# task_eagle.net
KiCad netlist of a schematic drawn in EAGLE
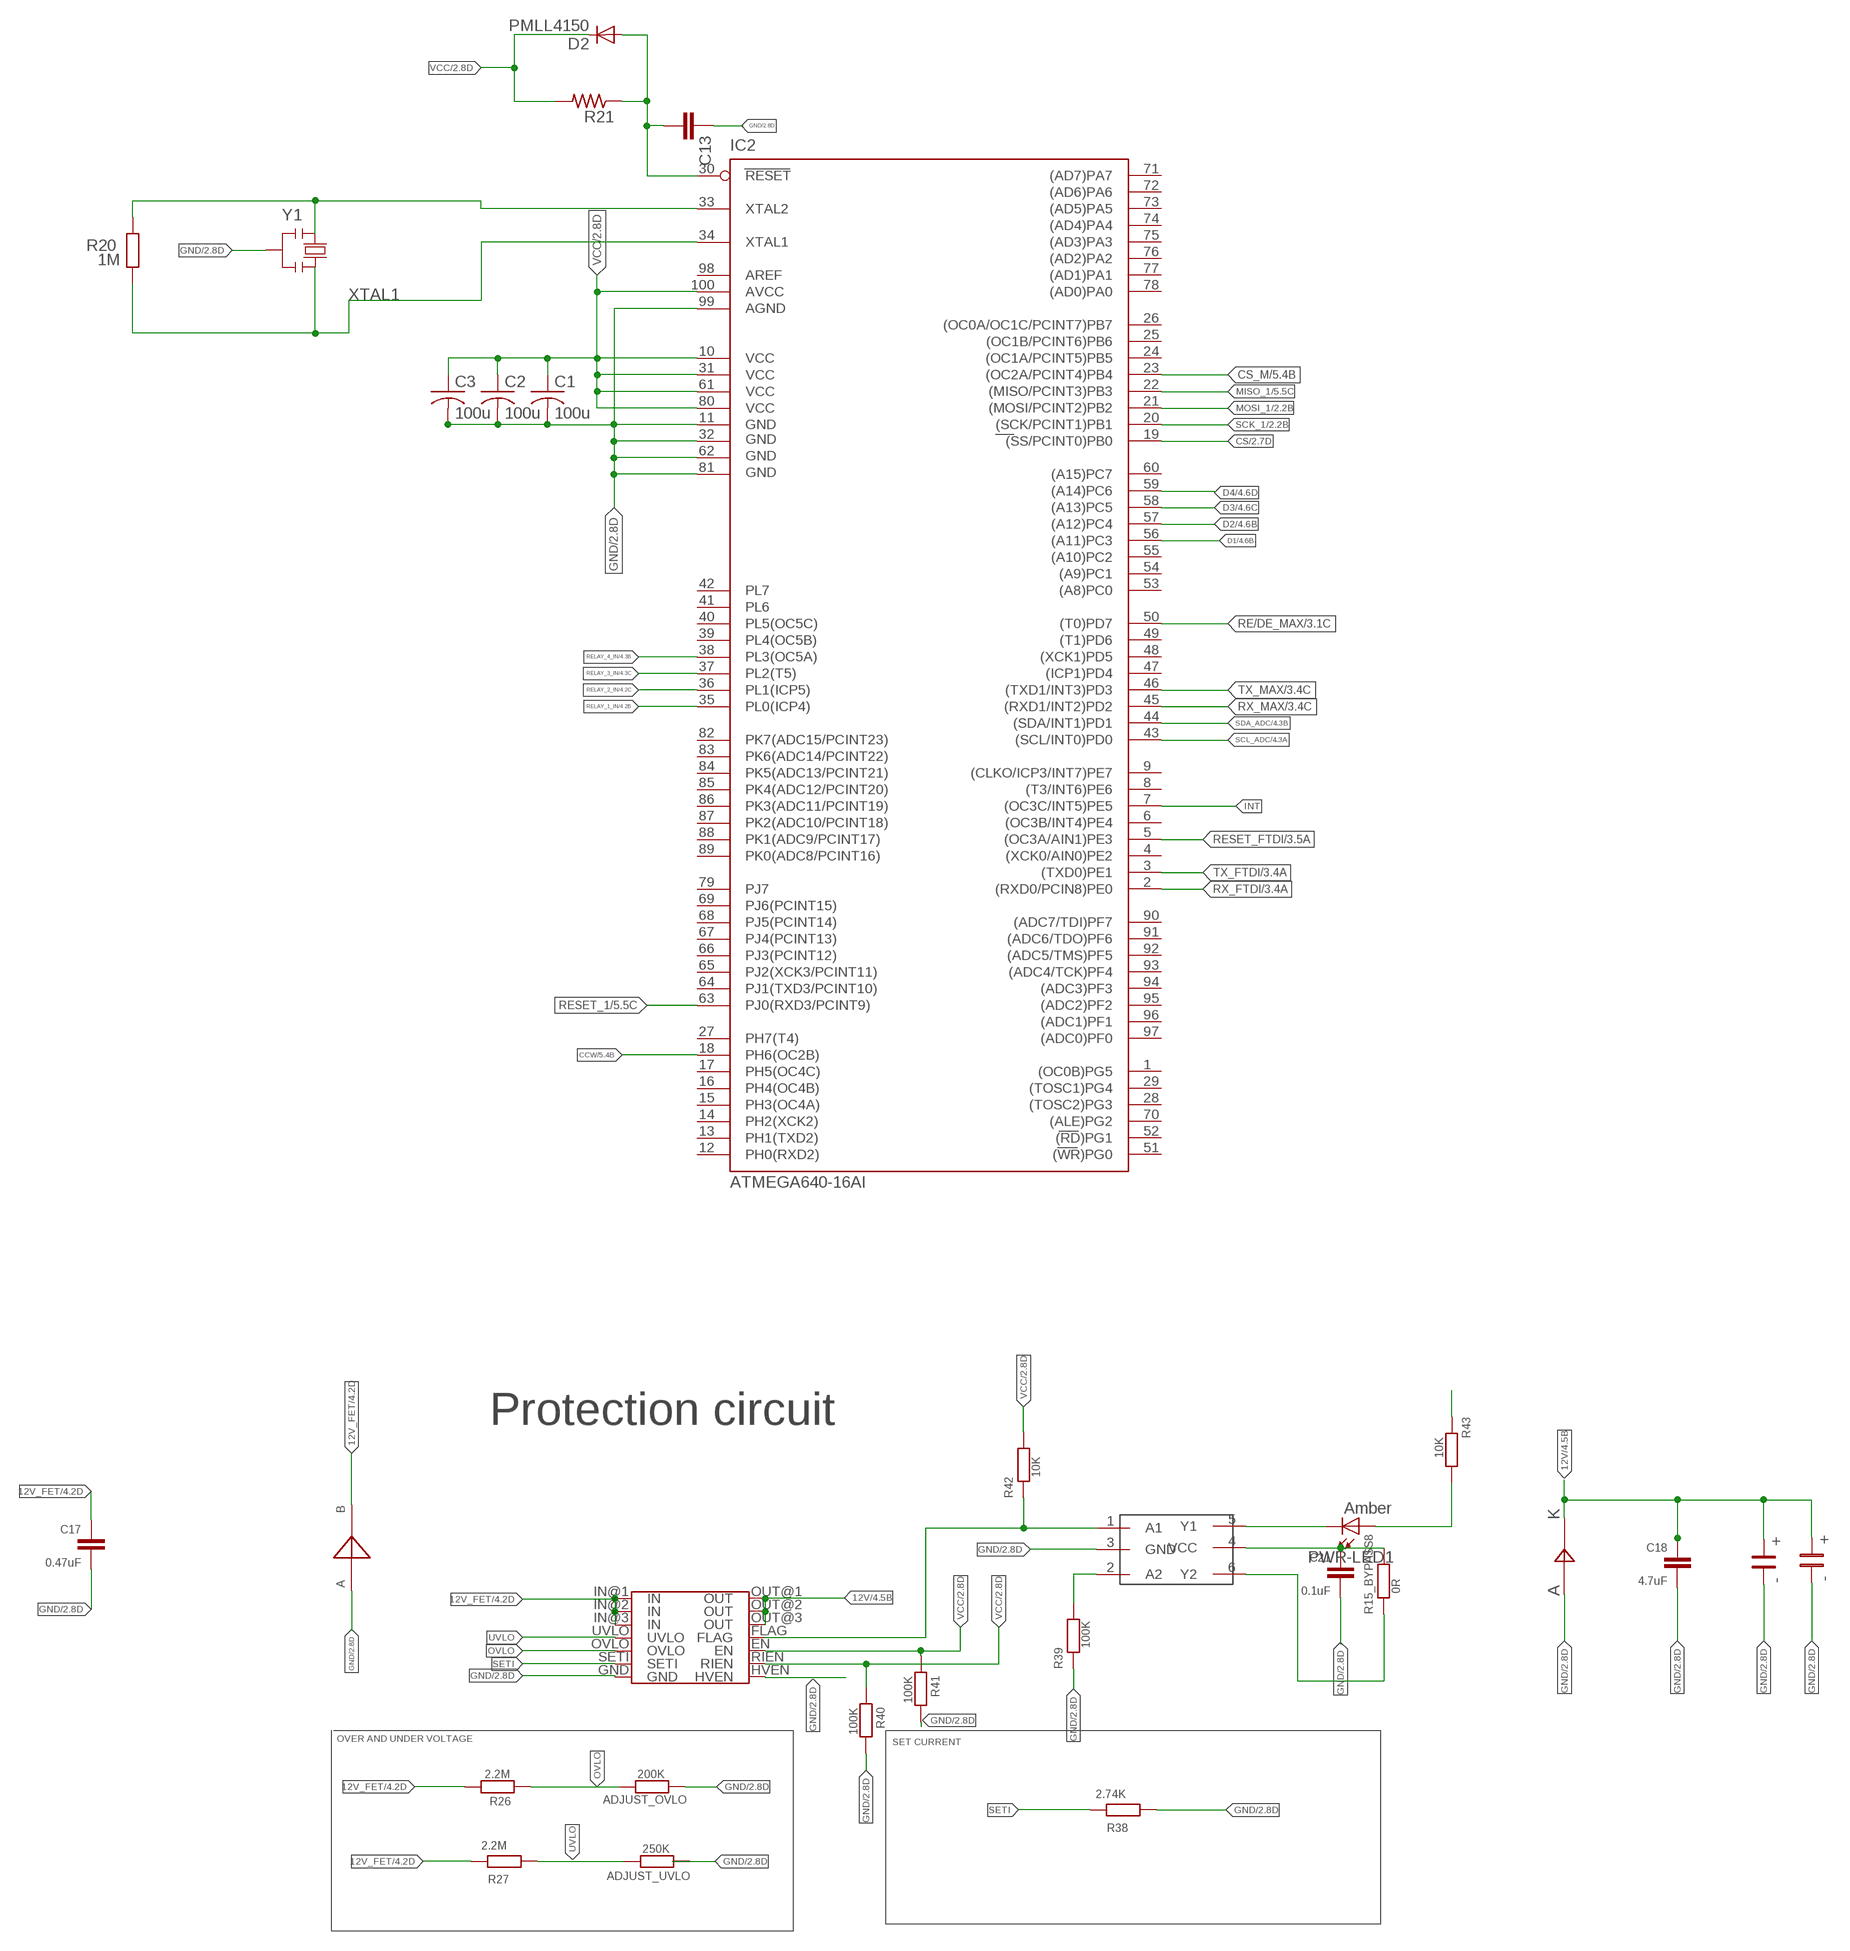
[diagram p0: schematic, sheet 1]
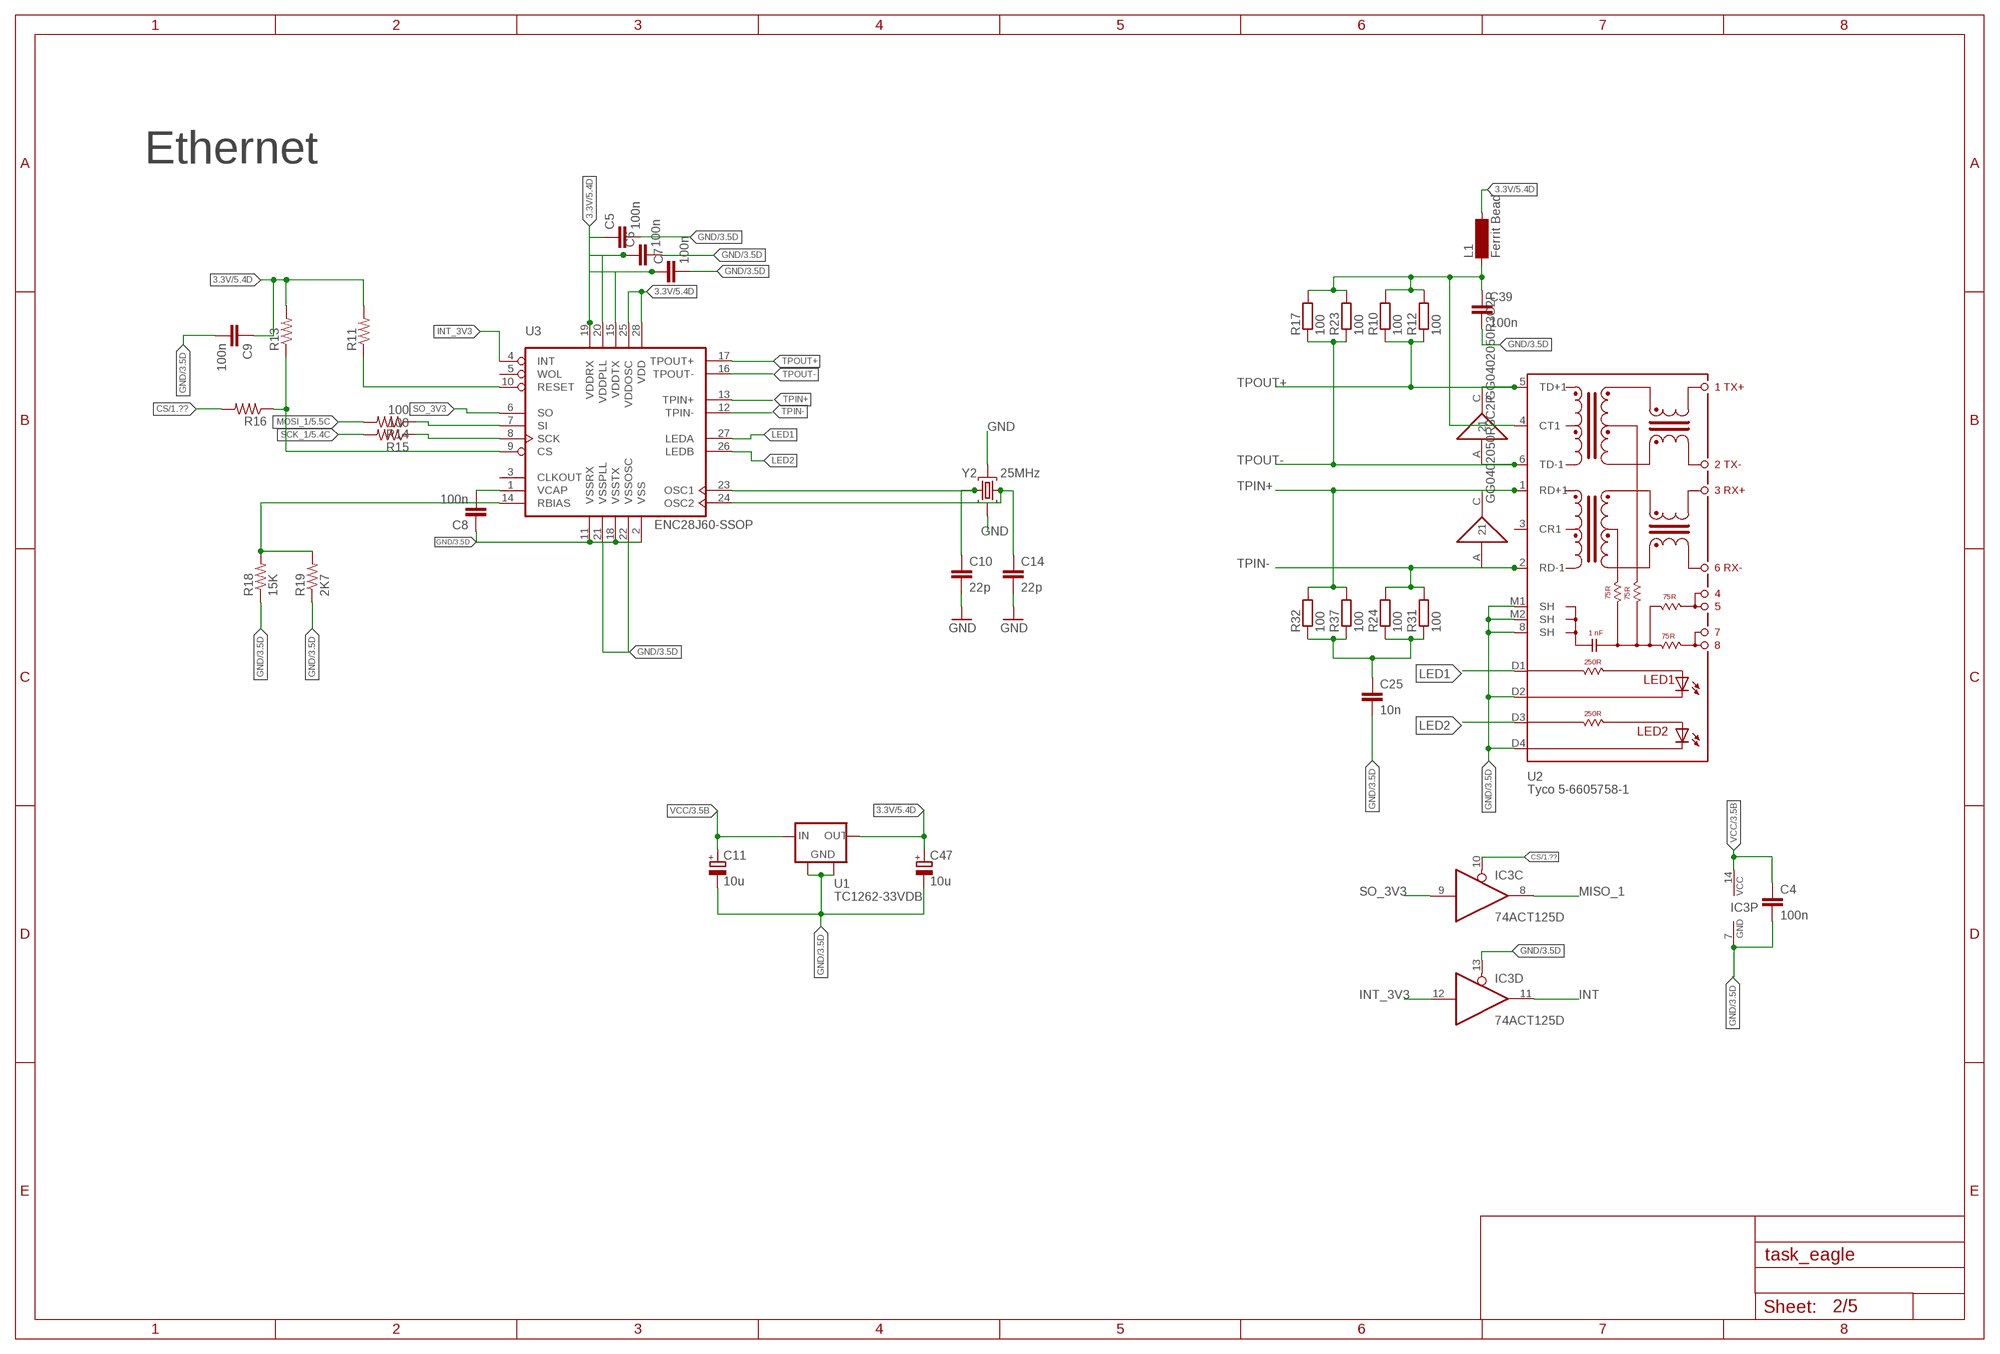
[diagram p1: schematic, sheet 2]
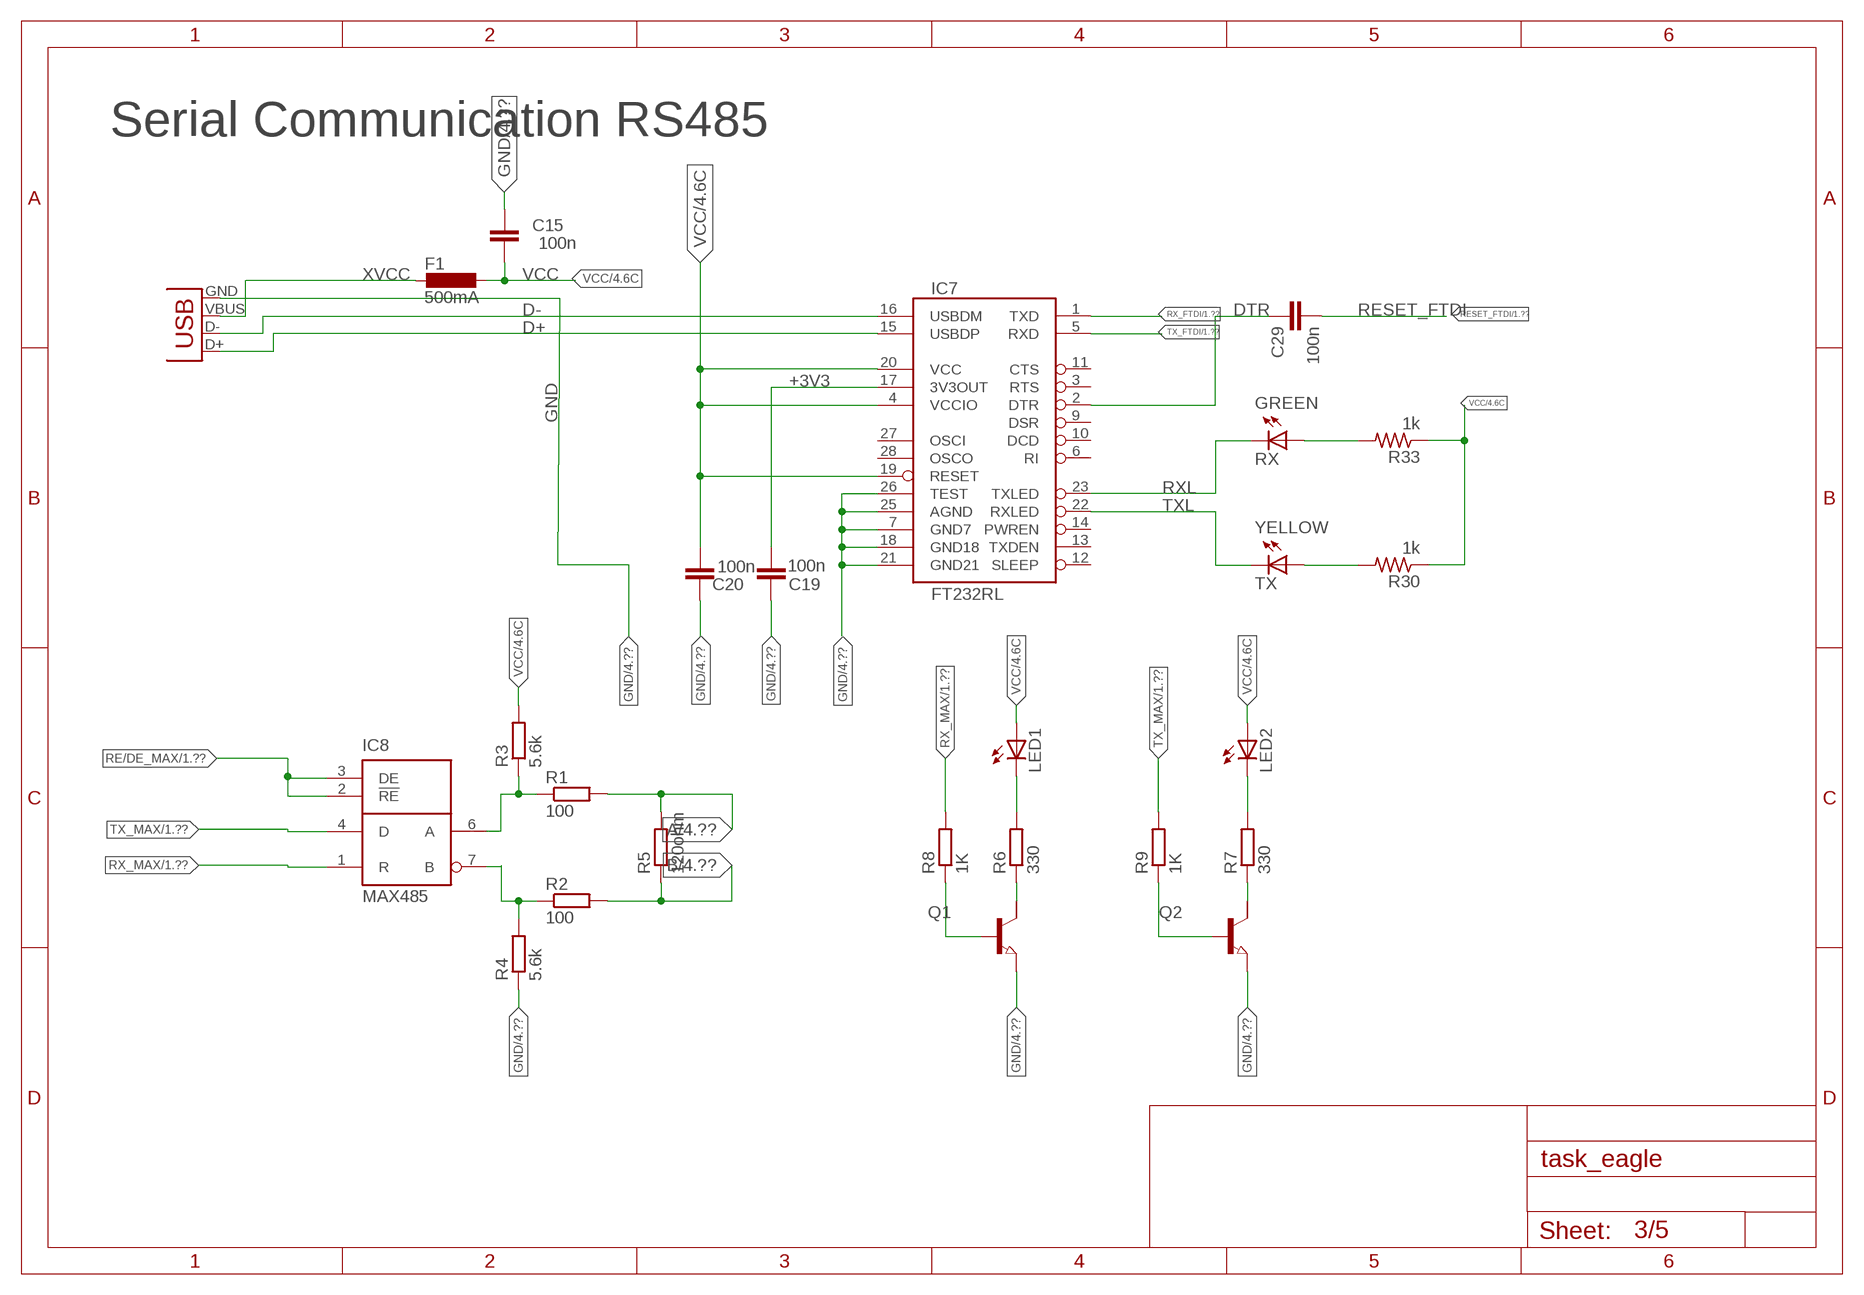
[diagram p2: schematic, sheet 3]
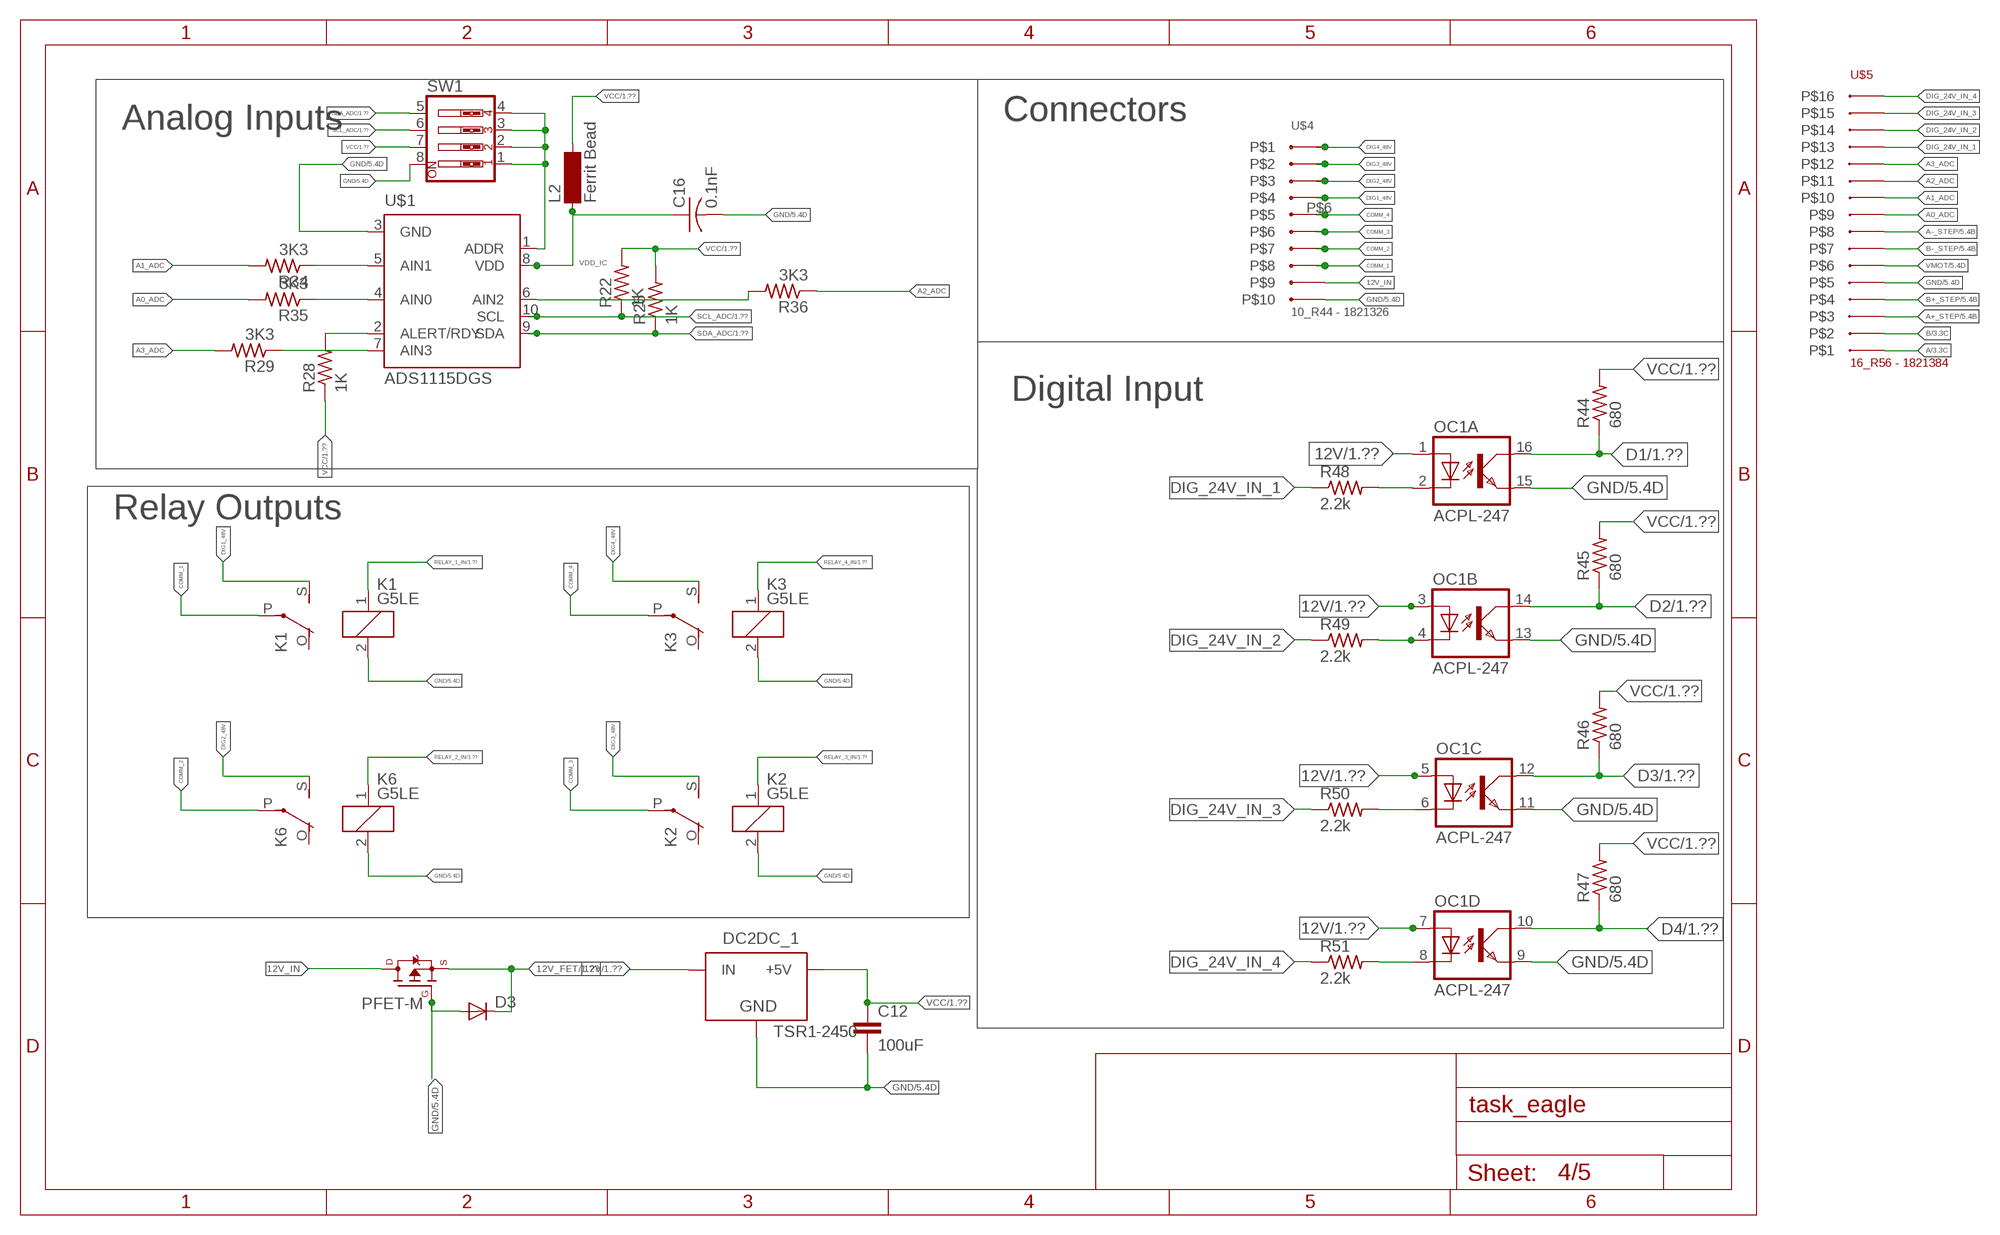
[diagram p3: schematic, sheet 4]
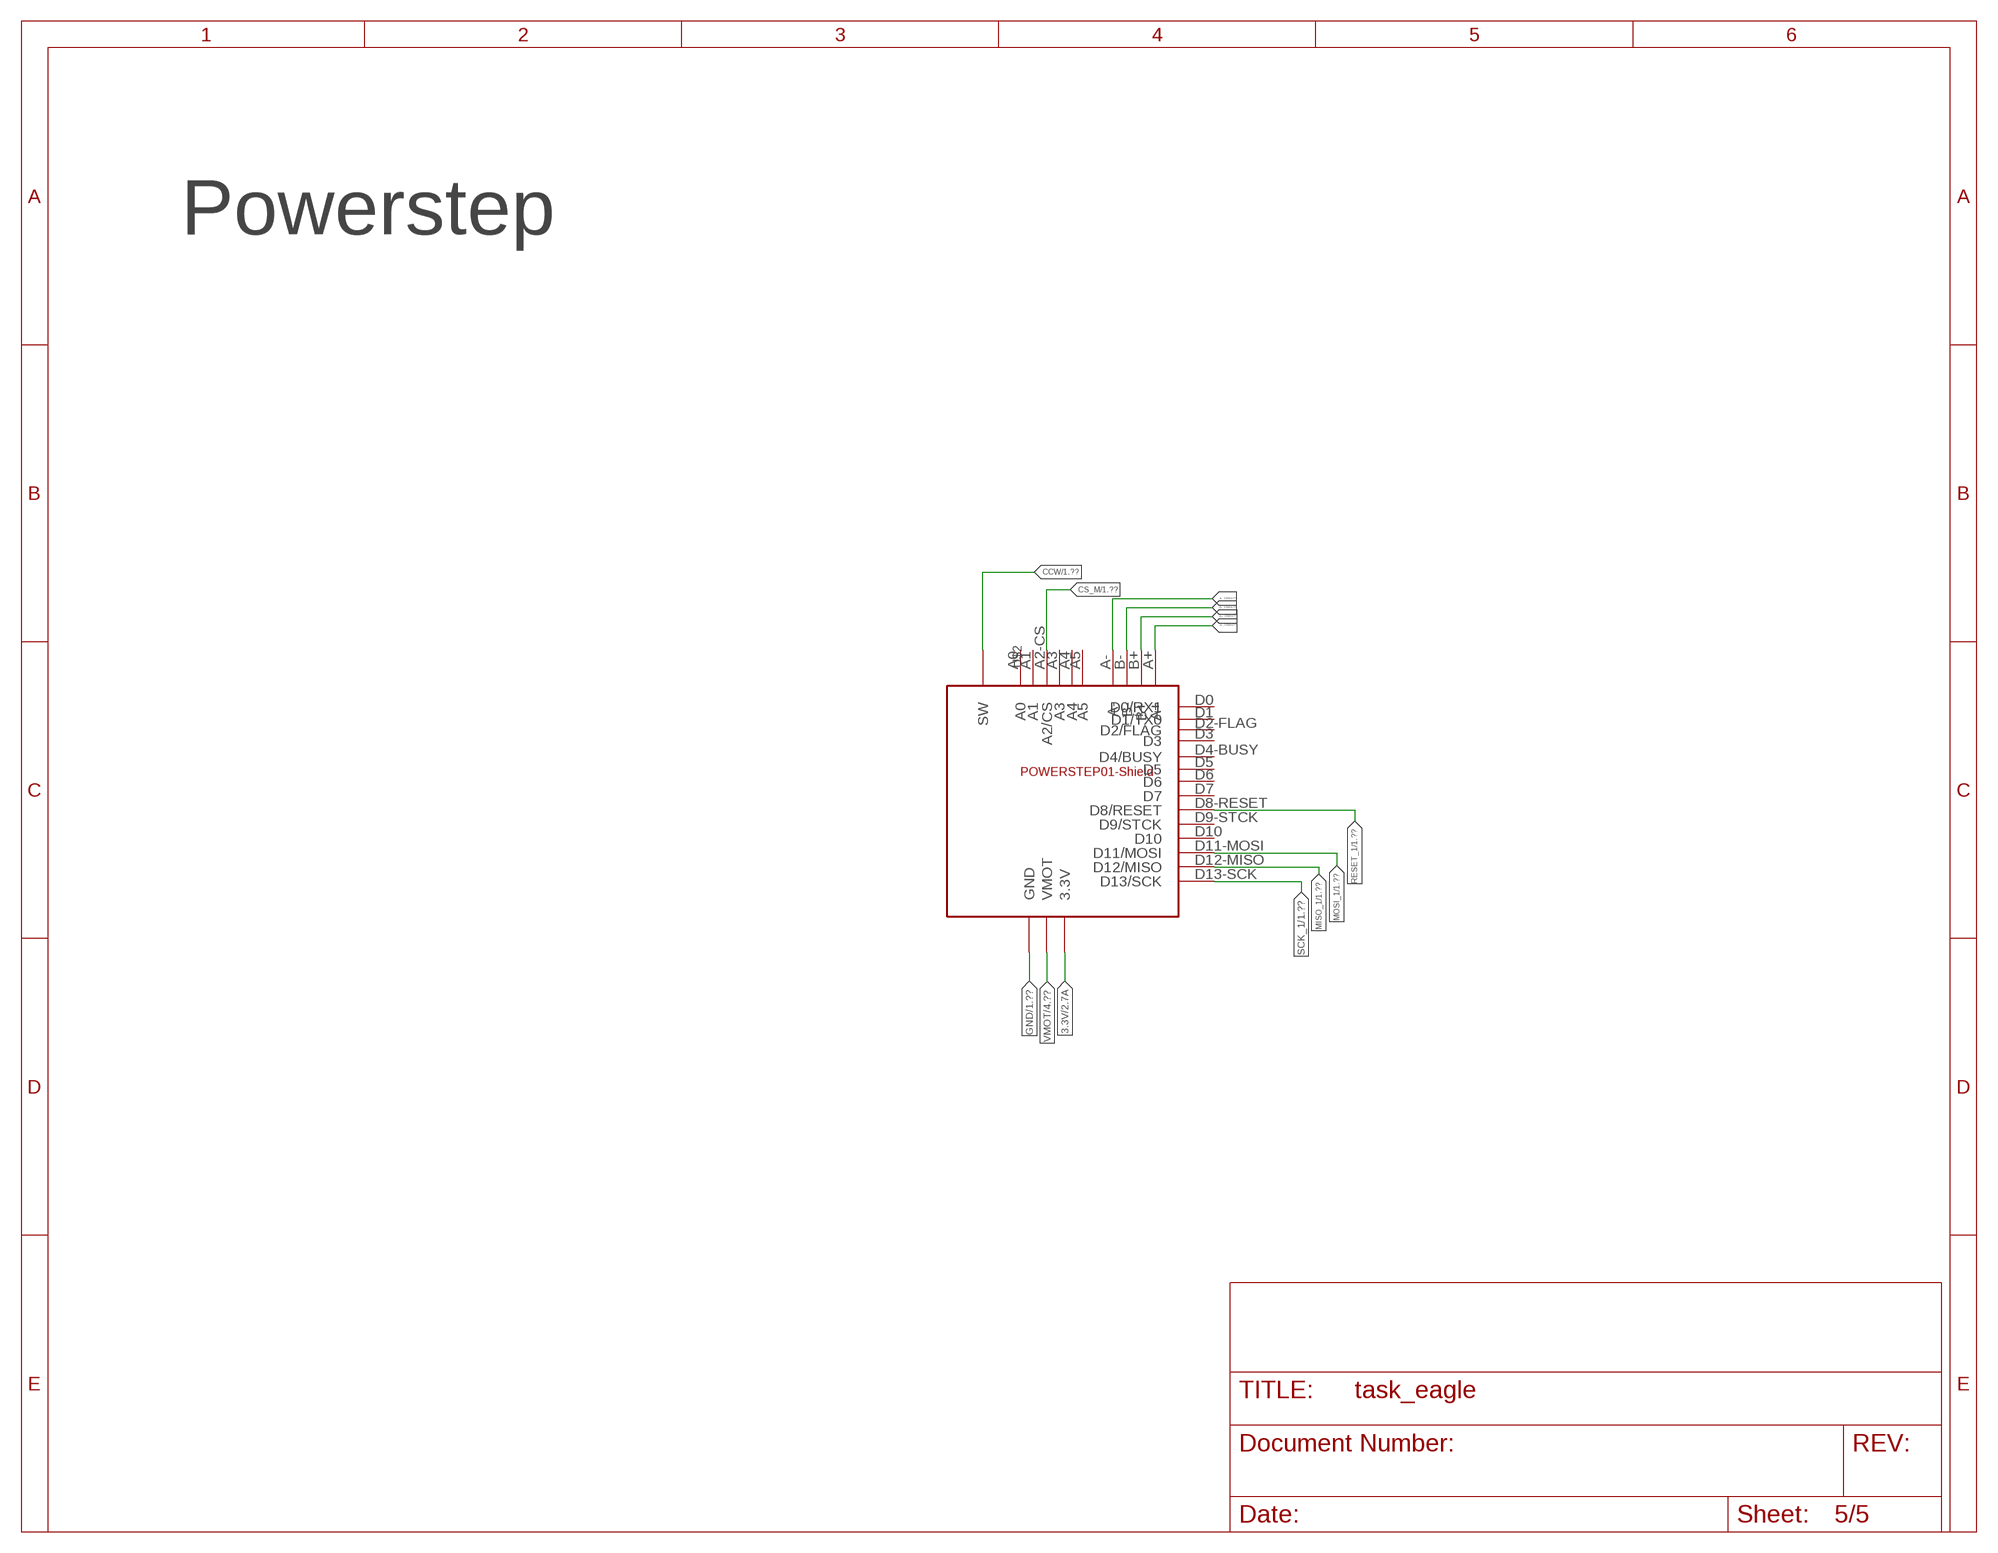
[diagram p4: schematic, sheet 5]

(export (version "E")
  (design (tool "Eeschema 10.0.6"))
  (components
    (comp (ref "C12")
      (value "100uF")
      (footprint "eagle-import:C0603")
      (libsource (lib "eagle-import") (part "CC0603"))
    )
    (comp (ref "C16")
      (value "0.1nF")
      (footprint "eagle-import:C0603")
      (libsource (lib "eagle-import") (part "C-USC0603"))
    )
    (comp (ref "D3")
      (value "DIODE-MINIMELF")
      (footprint "eagle-import:MINIMELF")
      (libsource (lib "eagle-import") (part "DIODE-MINIMELF"))
    )
    (comp (ref "DC2DC_1")
      (value "TSR1-2450")
      (footprint "eagle-import:TSR-1")
      (libsource (lib "eagle-import") (part "TSR1-2450"))
    )
    (comp (ref "K1")
      (value "G5LE")
      (footprint "eagle-import:G5LE")
      (libsource (lib "eagle-import") (part "G5LE"))
    )
    (comp (ref "K2")
      (value "G5LE")
      (footprint "eagle-import:G5LE")
      (libsource (lib "eagle-import") (part "G5LE"))
    )
    (comp (ref "K3")
      (value "G5LE")
      (footprint "eagle-import:G5LE")
      (libsource (lib "eagle-import") (part "G5LE"))
    )
    (comp (ref "K6")
      (value "G5LE")
      (footprint "eagle-import:G5LE")
      (libsource (lib "eagle-import") (part "G5LE"))
    )
    (comp (ref "L2")
      (value "Ferrit Bead")
      (footprint "eagle-import:SM-1206")
      (libsource (lib "eagle-import") (part "SM-1206"))
    )
    (comp (ref "OC1")
      (value "ACPL-247")
      (footprint "eagle-import:SOP16")
      (libsource (lib "eagle-import") (part "ACPL-247"))
    )
    (comp (ref "PFET-M")
      (value "FQP47P06NORMAL")
      (footprint "eagle-import:FQP47P06-NORMAL")
      (libsource (lib "eagle-import") (part "FQP47P06NORMAL"))
    )
    (comp (ref "R22")
      (value "1K")
      (footprint "eagle-import:R0603")
      (libsource (lib "eagle-import") (part "resistor_R-US_R0603"))
    )
    (comp (ref "R25")
      (value "1K")
      (footprint "eagle-import:R0603")
      (libsource (lib "eagle-import") (part "resistor_R-US_R0603"))
    )
    (comp (ref "R28")
      (value "1K")
      (footprint "eagle-import:R0603")
      (libsource (lib "eagle-import") (part "resistor_R-US_R0603"))
    )
    (comp (ref "R29")
      (value "3K3")
      (footprint "eagle-import:R0603")
      (libsource (lib "eagle-import") (part "resistor_R-US_R0603"))
    )
    (comp (ref "R34")
      (value "3K3")
      (footprint "eagle-import:R0603")
      (libsource (lib "eagle-import") (part "resistor_R-US_R0603"))
    )
    (comp (ref "R35")
      (value "3K3")
      (footprint "eagle-import:R0603")
      (libsource (lib "eagle-import") (part "resistor_R-US_R0603"))
    )
    (comp (ref "R36")
      (value "3K3")
      (footprint "eagle-import:R0603")
      (libsource (lib "eagle-import") (part "resistor_R-US_R0603"))
    )
    (comp (ref "R44")
      (value "680")
      (footprint "eagle-import:R0603")
      (libsource (lib "eagle-import") (part "R-US_R0603"))
    )
    (comp (ref "R45")
      (value "680")
      (footprint "eagle-import:R0603")
      (libsource (lib "eagle-import") (part "R-US_R0603"))
    )
    (comp (ref "R46")
      (value "680")
      (footprint "eagle-import:R0603")
      (libsource (lib "eagle-import") (part "R-US_R0603"))
    )
    (comp (ref "R47")
      (value "680")
      (footprint "eagle-import:R0603")
      (libsource (lib "eagle-import") (part "R-US_R0603"))
    )
    (comp (ref "R48")
      (value "2.2k")
      (footprint "eagle-import:R0603")
      (libsource (lib "eagle-import") (part "R-US_R0603"))
    )
    (comp (ref "R49")
      (value "2.2k")
      (footprint "eagle-import:R0603")
      (libsource (lib "eagle-import") (part "R-US_R0603"))
    )
    (comp (ref "R50")
      (value "2.2k")
      (footprint "eagle-import:R0603")
      (libsource (lib "eagle-import") (part "R-US_R0603"))
    )
    (comp (ref "R51")
      (value "2.2k")
      (footprint "eagle-import:R0603")
      (libsource (lib "eagle-import") (part "R-US_R0603"))
    )
    (comp (ref "SW1")
      (value "SW_DIP-4")
      (footprint "eagle-import:EDG-04")
      (libsource (lib "eagle-import") (part "SW_DIP-4"))
    )
    (comp (ref "U$1")
      (value "ADS1115DGS")
      (footprint "eagle-import:MSOP10")
      (libsource (lib "eagle-import") (part "ADS1115DGS"))
    )
    (comp (ref "U$4")
      (value "10_R44 - 1821326")
      (footprint "eagle-import:10_R44 - 1821326")
      (libsource (lib "eagle-import") (part "10_R44 - 1821326"))
    )
    (comp (ref "U$5")
      (value "16_R56 - 1821384")
      (footprint "eagle-import:16_R56 - 1821384")
      (libsource (lib "eagle-import") (part "16_R56 - 1821384"))
    )
    (comp (ref "ADJUST_OVLO")
      (value "200K")
      (footprint "eagle-import:R0603-ROUND")
      (libsource (lib "eagle-import") (part "R-EU_R0603"))
    )
    (comp (ref "ADJUST_UVLO")
      (value "250K")
      (footprint "eagle-import:R0603-ROUND")
      (libsource (lib "eagle-import") (part "R-EU_R0603"))
    )
    (comp (ref "C1")
      (value "100u")
      (footprint "eagle-import:C0603")
      (libsource (lib "eagle-import") (part "C-USC0603"))
    )
    (comp (ref "C2")
      (value "100u")
      (footprint "eagle-import:C0603")
      (libsource (lib "eagle-import") (part "C-USC0603"))
    )
    (comp (ref "C3")
      (value "100u")
      (footprint "eagle-import:C0603")
      (libsource (lib "eagle-import") (part "C-USC0603"))
    )
    (comp (ref "C13")
      (value "CC0603")
      (footprint "eagle-import:C0603")
      (libsource (lib "eagle-import") (part "CC0603"))
    )
    (comp (ref "C17")
      (value "0.47uF")
      (footprint "eagle-import:C0603-ROUND")
      (libsource (lib "eagle-import") (part "C-EU0603-RND"))
    )
    (comp (ref "C18")
      (value "4.7uF")
      (footprint "eagle-import:C0603-ROUND")
      (libsource (lib "eagle-import") (part "C-EU0603-RND"))
    )
    (comp (ref "C21")
      (value "0.1uF")
      (footprint "eagle-import:C0603-ROUND")
      (libsource (lib "eagle-import") (part "C-EU0603-RND"))
    )
    (comp (ref "D2")
      (value "PMLL4150")
      (footprint "eagle-import:SOD80C")
      (libsource (lib "eagle-import") (part "PMLL4150"))
    )
    (comp (ref "IC2")
      (value "ATMEGA640-16AI")
      (footprint "eagle-import:TQFP100")
      (libsource (lib "eagle-import") (part "ATMEGAAI640-16"))
    )
    (comp (ref "PWR-LED1")
      (value "Amber")
      (footprint "eagle-import:LED-0603")
      (libsource (lib "eagle-import") (part "LED0603"))
    )
    (comp (ref "R15_BYPASS8")
      (value "0R")
      (footprint "eagle-import:R0603-ROUND")
      (libsource (lib "eagle-import") (part "R-EU_R0603"))
    )
    (comp (ref "R20")
      (value "1M")
      (footprint "eagle-import:R0603-ROUND")
      (libsource (lib "eagle-import") (part "R-EU_R0603"))
    )
    (comp (ref "R21")
      (value "R-US_R0603")
      (footprint "eagle-import:R0603")
      (libsource (lib "eagle-import") (part "resistor_R-US_R0603"))
    )
    (comp (ref "R26")
      (value "2.2M")
      (footprint "eagle-import:R0603-ROUND")
      (libsource (lib "eagle-import") (part "R-EU_R0603"))
    )
    (comp (ref "R27")
      (value "2.2M")
      (footprint "eagle-import:R0603-ROUND")
      (libsource (lib "eagle-import") (part "R-EU_R0603"))
    )
    (comp (ref "R38")
      (value "2.74K")
      (footprint "eagle-import:R0603-ROUND")
      (libsource (lib "eagle-import") (part "R-EU_R0603"))
    )
    (comp (ref "R39")
      (value "100K")
      (footprint "eagle-import:R0603-ROUND")
      (libsource (lib "eagle-import") (part "R-EU_R0603"))
    )
    (comp (ref "R40")
      (value "100K")
      (footprint "eagle-import:R0603-ROUND")
      (libsource (lib "eagle-import") (part "R-EU_R0603"))
    )
    (comp (ref "R41")
      (value "100K")
      (footprint "eagle-import:R0603-ROUND")
      (libsource (lib "eagle-import") (part "R-EU_R0603"))
    )
    (comp (ref "R42")
      (value "10K")
      (footprint "eagle-import:R0603-ROUND")
      (libsource (lib "eagle-import") (part "R-EU_R0603"))
    )
    (comp (ref "R43")
      (value "10K")
      (footprint "eagle-import:R0603-ROUND")
      (libsource (lib "eagle-import") (part "R-EU_R0603"))
    )
    (comp (ref "U$37")
      (value "MAX14571")
      (footprint "eagle-import:TSSOP14")
      (libsource (lib "eagle-import") (part "MAX14571"))
    )
    (comp (ref "U$38")
      (value "STPS5L60S")
      (footprint "eagle-import:SMC")
      (libsource (lib "eagle-import") (part "STPS5L60S"))
    )
    (comp (ref "U$39")
      (value "SM6T36CA")
      (footprint "eagle-import:DO214AA")
      (libsource (lib "eagle-import") (part "SM6T36CA"))
    )
    (comp (ref "U$40")
      (value "NC7WZ07P6X")
      (footprint "eagle-import:SC70-6L")
      (libsource (lib "eagle-import") (part "NC7WZ07P6X"))
    )
    (comp (ref "U$41")
      (value "EEV-FK1H331Q")
      (footprint "eagle-import:EEVFK1H331Q")
      (libsource (lib "eagle-import") (part "EEV-FK1H331Q"))
    )
    (comp (ref "U$42")
      (value "EEV-FK1H331Q")
      (footprint "eagle-import:EEVFK1H331Q")
      (libsource (lib "eagle-import") (part "EEV-FK1H331Q"))
    )
    (comp (ref "Y1")
      (value "RESONATORMU")
      (footprint "eagle-import:RESONATOR")
      (libsource (lib "eagle-import") (part "RESONATORMU"))
    )
    (comp (ref "U$2")
      (value "POWERSTEP01-SHIELD")
      (footprint "eagle-import:POWERSTEP1")
      (libsource (lib "eagle-import") (part "POWERSTEP01-SHIELD"))
    )
    (comp (ref "C15")
      (value "100n")
      (footprint "eagle-import:C0603")
      (libsource (lib "eagle-import") (part "rcl_C-EUC0603"))
    )
    (comp (ref "C19")
      (value "100n")
      (footprint "eagle-import:C0603-ROUND")
      (libsource (lib "eagle-import") (part "C-EU0603-RND"))
    )
    (comp (ref "C20")
      (value "100n")
      (footprint "eagle-import:C0603-ROUND")
      (libsource (lib "eagle-import") (part "C-EU0603-RND"))
    )
    (comp (ref "C29")
      (value "100n")
      (footprint "eagle-import:C0603-ROUND")
      (libsource (lib "eagle-import") (part "C-EU0603-RND"))
    )
    (comp (ref "F1")
      (value "500mA")
      (footprint "eagle-import:L1812")
      (libsource (lib "eagle-import") (part "L-EUL1812"))
    )
    (comp (ref "IC7")
      (value "FT232RL")
      (footprint "eagle-import:SSOP28DB")
      (libsource (lib "eagle-import") (part "FT232RLSSOP"))
    )
    (comp (ref "IC8")
      (value "MAX485")
      (footprint "eagle-import:SO-08")
      (fields (field (name "MF") "TEXAS INSTRUMENTS") (field (name "MPN") "SN75ALS176AD"))
      (libsource (lib "eagle-import") (part "75ALS176DA"))
    )
    (comp (ref "LED1")
      (value "LED_ESML0603")
      (footprint "eagle-import:LED_SML0603")
      (libsource (lib "eagle-import") (part "LED_ESML0603"))
    )
    (comp (ref "LED2")
      (value "LED_ESML0603")
      (footprint "eagle-import:LED_SML0603")
      (libsource (lib "eagle-import") (part "LED_ESML0603"))
    )
    (comp (ref "Q1")
      (value "NPN-TRANSISTIOR-2COLSOT89")
      (footprint "eagle-import:SOT89")
      (libsource (lib "eagle-import") (part "NPN-TRANSISTIOR-2COLSOT89"))
    )
    (comp (ref "Q2")
      (value "NPN-TRANSISTIOR-2COLSOT89")
      (footprint "eagle-import:SOT89")
      (libsource (lib "eagle-import") (part "NPN-TRANSISTIOR-2COLSOT89"))
    )
    (comp (ref "R1")
      (value "100")
      (footprint "eagle-import:R0603")
      (libsource (lib "eagle-import") (part "RR0603"))
    )
    (comp (ref "R2")
      (value "100")
      (footprint "eagle-import:R0603")
      (libsource (lib "eagle-import") (part "RR0603"))
    )
    (comp (ref "R3")
      (value "5.6k")
      (footprint "eagle-import:R0603")
      (libsource (lib "eagle-import") (part "RR0603"))
    )
    (comp (ref "R4")
      (value "5.6k")
      (footprint "eagle-import:R0603")
      (libsource (lib "eagle-import") (part "RR0603"))
    )
    (comp (ref "R5")
      (value "120ohm")
      (footprint "eagle-import:R0603")
      (libsource (lib "eagle-import") (part "RR0603"))
    )
    (comp (ref "R6")
      (value "330")
      (footprint "eagle-import:R0603")
      (libsource (lib "eagle-import") (part "RR0603"))
    )
    (comp (ref "R7")
      (value "330")
      (footprint "eagle-import:R0603")
      (libsource (lib "eagle-import") (part "RR0603"))
    )
    (comp (ref "R8")
      (value "1K")
      (footprint "eagle-import:R0603")
      (libsource (lib "eagle-import") (part "RR0603"))
    )
    (comp (ref "R9")
      (value "1K")
      (footprint "eagle-import:R0603")
      (libsource (lib "eagle-import") (part "RR0603"))
    )
    (comp (ref "R30")
      (value "1k")
      (footprint "eagle-import:R0603")
      (libsource (lib "eagle-import") (part "resistor_R-US_R0603"))
    )
    (comp (ref "R33")
      (value "1k")
      (footprint "eagle-import:R0603")
      (libsource (lib "eagle-import") (part "resistor_R-US_R0603"))
    )
    (comp (ref "RX")
      (value "GREEN")
      (footprint "eagle-import:CHIPLED_0603")
      (libsource (lib "eagle-import") (part "LEDCHIPLED_0603"))
    )
    (comp (ref "TX")
      (value "YELLOW")
      (footprint "eagle-import:CHIPLED_0603")
      (libsource (lib "eagle-import") (part "LEDCHIPLED_0603"))
    )
    (comp (ref "USB")
      (value "USB")
      (footprint "eagle-import:USB-B-PTH-VERTICAL")
      (libsource (lib "eagle-import") (part "USBPTH-VERTICAL"))
    )
    (comp (ref "C4")
      (value "100n")
      (footprint "eagle-import:C0603")
      (libsource (lib "eagle-import") (part "rcl_C-EUC0603"))
    )
    (comp (ref "C5")
      (value "100n")
      (footprint "eagle-import:C0603")
      (libsource (lib "eagle-import") (part "rcl_C-EUC0603"))
    )
    (comp (ref "C6")
      (value "100n")
      (footprint "eagle-import:C0603")
      (libsource (lib "eagle-import") (part "rcl_C-EUC0603"))
    )
    (comp (ref "C7")
      (value "100n")
      (footprint "eagle-import:C0603")
      (libsource (lib "eagle-import") (part "rcl_C-EUC0603"))
    )
    (comp (ref "C8")
      (value "100n")
      (footprint "eagle-import:C0603")
      (libsource (lib "eagle-import") (part "rcl_C-EUC0603"))
    )
    (comp (ref "C9")
      (value "100n")
      (footprint "eagle-import:C0603")
      (libsource (lib "eagle-import") (part "rcl_C-EUC0603"))
    )
    (comp (ref "C10")
      (value "22p")
      (footprint "eagle-import:C0603")
      (libsource (lib "eagle-import") (part "rcl_C-EUC0603"))
    )
    (comp (ref "C11")
      (value "10u")
      (footprint "eagle-import:153CLV-0605")
      (libsource (lib "eagle-import") (part "CPOL-EU153CLV-0605"))
    )
    (comp (ref "C14")
      (value "22p")
      (footprint "eagle-import:C0603")
      (libsource (lib "eagle-import") (part "rcl_C-EUC0603"))
    )
    (comp (ref "C25")
      (value "10n")
      (footprint "eagle-import:C0603")
      (libsource (lib "eagle-import") (part "rcl_C-EUC0603"))
    )
    (comp (ref "C39")
      (value "100n")
      (footprint "eagle-import:C0603")
      (libsource (lib "eagle-import") (part "rcl_C-EUC0603"))
    )
    (comp (ref "C47")
      (value "10u")
      (footprint "eagle-import:153CLV-0605")
      (libsource (lib "eagle-import") (part "CPOL-EU153CLV-0605"))
    )
    (comp (ref "IC3")
      (value "74ACT125D")
      (footprint "eagle-import:SO14")
      (libsource (lib "eagle-import") (part "74125DACT"))
    )
    (comp (ref "L1")
      (value "Ferrit Bead")
      (footprint "eagle-import:SM-1206")
      (libsource (lib "eagle-import") (part "SM-1206"))
    )
    (comp (ref "R10")
      (value "100")
      (footprint "eagle-import:R0603")
      (libsource (lib "eagle-import") (part "rcl_R-EU_R0603"))
    )
    (comp (ref "R11")
      (value "R-US_R0603")
      (footprint "eagle-import:R0603")
      (libsource (lib "eagle-import") (part "R-US_R0603"))
    )
    (comp (ref "R12")
      (value "100")
      (footprint "eagle-import:R0603")
      (libsource (lib "eagle-import") (part "rcl_R-EU_R0603"))
    )
    (comp (ref "R13")
      (value "R-US_R0603")
      (footprint "eagle-import:R0603")
      (libsource (lib "eagle-import") (part "R-US_R0603"))
    )
    (comp (ref "R14")
      (value "100")
      (footprint "eagle-import:R0603")
      (libsource (lib "eagle-import") (part "R-US_R0603"))
    )
    (comp (ref "R15")
      (value "100")
      (footprint "eagle-import:R0603")
      (libsource (lib "eagle-import") (part "R-US_R0603"))
    )
    (comp (ref "R16")
      (value "R-US_R0603")
      (footprint "eagle-import:R0603")
      (libsource (lib "eagle-import") (part "R-US_R0603"))
    )
    (comp (ref "R17")
      (value "100")
      (footprint "eagle-import:R0603")
      (libsource (lib "eagle-import") (part "rcl_R-EU_R0603"))
    )
    (comp (ref "R18")
      (value "15K")
      (footprint "eagle-import:R0603")
      (libsource (lib "eagle-import") (part "R-US_R0603"))
    )
    (comp (ref "R19")
      (value "2K7")
      (footprint "eagle-import:R0603")
      (libsource (lib "eagle-import") (part "R-US_R0603"))
    )
    (comp (ref "R23")
      (value "100")
      (footprint "eagle-import:R0603")
      (libsource (lib "eagle-import") (part "rcl_R-EU_R0603"))
    )
    (comp (ref "R24")
      (value "100")
      (footprint "eagle-import:R0603")
      (libsource (lib "eagle-import") (part "rcl_R-EU_R0603"))
    )
    (comp (ref "R31")
      (value "100")
      (footprint "eagle-import:R0603")
      (libsource (lib "eagle-import") (part "rcl_R-EU_R0603"))
    )
    (comp (ref "R32")
      (value "100")
      (footprint "eagle-import:R0603")
      (libsource (lib "eagle-import") (part "rcl_R-EU_R0603"))
    )
    (comp (ref "R37")
      (value "100")
      (footprint "eagle-import:R0603")
      (libsource (lib "eagle-import") (part "rcl_R-EU_R0603"))
    )
    (comp (ref "U$6")
      (value "GG0402050R3C2P")
      (footprint "eagle-import:0402")
      (libsource (lib "eagle-import") (part "GG0402050R3C2P"))
    )
    (comp (ref "U$7")
      (value "GG0402050R3C2P")
      (footprint "eagle-import:0402")
      (libsource (lib "eagle-import") (part "GG0402050R3C2P"))
    )
    (comp (ref "U1")
      (value "TC1262-33VDB")
      (footprint "eagle-import:SOT223")
      (libsource (lib "eagle-import") (part "TC1262-50VDB"))
    )
    (comp (ref "U2")
      (value "Tyco 5-6605758-1")
      (footprint "eagle-import:5-6605758-1")
      (libsource (lib "eagle-import") (part "5-6605758-1"))
    )
    (comp (ref "U3")
      (value "ENC28J60-SSOP")
      (footprint "eagle-import:SSOP28")
      (libsource (lib "eagle-import") (part "ENC28J60-SSOP"))
    )
    (comp (ref "Y2")
      (value "25MHz")
      (footprint "eagle-import:CRYSTAL-3.2-2.5")
      (libsource (lib "eagle-import") (part "CRYSTAL-3.2-2.5"))
    )
  )
  (nets
    (net (code "1") (name "+3V3") (class "Default")
      (node (ref "C19") (pin "2") (pinfunction "2_2") (pintype "passive"))
      (node (ref "IC7") (pin "17") (pinfunction "3V3OUT_17") (pintype "output"))
    )
    (net (code "2") (name "3.3V") (class "Default")
      (node (ref "C47") (pin "+") (pinfunction "+_+") (pintype "passive"))
      (node (ref "C5") (pin "1") (pinfunction "1_1") (pintype "passive"))
      (node (ref "C6") (pin "1") (pinfunction "1_1") (pintype "passive"))
      (node (ref "C7") (pin "1") (pinfunction "1_1") (pintype "passive"))
      (node (ref "C9") (pin "1") (pinfunction "1_1") (pintype "passive"))
      (node (ref "L1") (pin "2") (pinfunction "2_2") (pintype "passive"))
      (node (ref "R11") (pin "2") (pinfunction "2_2") (pintype "passive"))
      (node (ref "R13") (pin "2") (pinfunction "2_2") (pintype "passive"))
      (node (ref "U$2") (pin "3.3V") (pinfunction "3.3V_3.3V") (pintype "power_in"))
      (node (ref "U$2") (pin "IOREF") (pinfunction "3.3V_IOREF") (pintype "power_in"))
      (node (ref "U1") (pin "3") (pinfunction "OUT_3") (pintype "passive"))
      (node (ref "U3") (pin "15") (pinfunction "VDDTX_15") (pintype "power_in"))
      (node (ref "U3") (pin "19") (pinfunction "VDDRX_19") (pintype "power_in"))
      (node (ref "U3") (pin "20") (pinfunction "VDDPLL_20") (pintype "power_in"))
      (node (ref "U3") (pin "25") (pinfunction "VDDOSC_25") (pintype "power_in"))
      (node (ref "U3") (pin "28") (pinfunction "VDD_28") (pintype "power_in"))
    )
    (net (code "3") (name "12V") (class "Default")
      (node (ref "C18") (pin "1") (pinfunction "1_1") (pintype "passive"))
      (node (ref "DC2DC_1") (pin "1") (pinfunction "IN_1") (pintype "power_in"))
      (node (ref "OC1") (pin "1") (pinfunction "A_1") (pintype "passive"))
      (node (ref "OC1") (pin "3") (pinfunction "A_3") (pintype "passive"))
      (node (ref "OC1") (pin "5") (pinfunction "A_5") (pintype "passive"))
      (node (ref "OC1") (pin "7") (pinfunction "A_7") (pintype "passive"))
      (node (ref "U$37") (pin "OUT@1") (pinfunction "OUT_OUT@1") (pintype "bidirectional"))
      (node (ref "U$37") (pin "OUT@2") (pinfunction "OUT_OUT@2") (pintype "bidirectional"))
      (node (ref "U$37") (pin "OUT@3") (pinfunction "OUT_OUT@3") (pintype "bidirectional"))
      (node (ref "U$38") (pin "1") (pinfunction "P$2_1") (pintype "bidirectional"))
      (node (ref "U$41") (pin "P$2") (pinfunction "P$1_P$2") (pintype "bidirectional"))
      (node (ref "U$42") (pin "P$2") (pinfunction "P$1_P$2") (pintype "bidirectional"))
    )
    (net (code "4") (name "12V_FET") (class "Default")
      (node (ref "C17") (pin "1") (pinfunction "1_1") (pintype "passive"))
      (node (ref "D3") (pin "C") (pinfunction "C_C") (pintype "passive"))
      (node (ref "PFET-M") (pin "3") (pinfunction "S_3") (pintype "passive"))
      (node (ref "R26") (pin "1") (pinfunction "1_1") (pintype "passive"))
      (node (ref "R27") (pin "1") (pinfunction "1_1") (pintype "passive"))
      (node (ref "U$37") (pin "IN@1") (pinfunction "IN_IN@1") (pintype "bidirectional"))
      (node (ref "U$37") (pin "IN@2") (pinfunction "IN_IN@2") (pintype "bidirectional"))
      (node (ref "U$37") (pin "IN@3") (pinfunction "IN_IN@3") (pintype "bidirectional"))
      (node (ref "U$39") (pin "C") (pinfunction "P$2_C") (pintype "bidirectional"))
    )
    (net (code "5") (name "12V_IN") (class "Default")
      (node (ref "PFET-M") (pin "2") (pinfunction "D_2") (pintype "passive"))
      (node (ref "U$4") (pin "P$10") (pinfunction "P$9_P$10") (pintype "bidirectional"))
    )
    (net (code "6") (name "A") (class "Default")
      (node (ref "R1") (pin "2") (pinfunction "2_2") (pintype "passive"))
      (node (ref "R5") (pin "2") (pinfunction "2_2") (pintype "passive"))
      (node (ref "U$5") (pin "P$1") (pinfunction "P$1_P$1") (pintype "bidirectional"))
    )
    (net (code "7") (name "A+_STEP") (class "Default")
      (node (ref "U$2") (pin "A+") (pinfunction "A+_A+") (pintype "bidirectional"))
      (node (ref "U$5") (pin "P$3") (pinfunction "P$3_P$3") (pintype "bidirectional"))
    )
    (net (code "8") (name "A-_STEP") (class "Default")
      (node (ref "U$2") (pin "A-") (pinfunction "A-_A-") (pintype "bidirectional"))
      (node (ref "U$5") (pin "P$8") (pinfunction "P$8_P$8") (pintype "bidirectional"))
    )
    (net (code "9") (name "A0_ADC") (class "Default")
      (node (ref "R35") (pin "2") (pinfunction "2_2") (pintype "passive"))
      (node (ref "U$5") (pin "P$9") (pinfunction "P$9_P$9") (pintype "bidirectional"))
    )
    (net (code "10") (name "A1_ADC") (class "Default")
      (node (ref "R34") (pin "2") (pinfunction "2_2") (pintype "passive"))
      (node (ref "U$5") (pin "P$10") (pinfunction "P$10_P$10") (pintype "bidirectional"))
    )
    (net (code "11") (name "A2_ADC") (class "Default")
      (node (ref "R36") (pin "1") (pinfunction "1_1") (pintype "passive"))
      (node (ref "U$5") (pin "P$11") (pinfunction "P$11_P$11") (pintype "bidirectional"))
    )
    (net (code "12") (name "A3_ADC") (class "Default")
      (node (ref "R29") (pin "2") (pinfunction "2_2") (pintype "passive"))
      (node (ref "U$5") (pin "P$12") (pinfunction "P$12_P$12") (pintype "bidirectional"))
    )
    (net (code "13") (name "B") (class "Default")
      (node (ref "R2") (pin "2") (pinfunction "2_2") (pintype "passive"))
      (node (ref "R5") (pin "1") (pinfunction "1_1") (pintype "passive"))
      (node (ref "U$5") (pin "P$2") (pinfunction "P$2_P$2") (pintype "bidirectional"))
    )
    (net (code "14") (name "B+_STEP") (class "Default")
      (node (ref "U$2") (pin "B+") (pinfunction "B+_B+") (pintype "bidirectional"))
      (node (ref "U$5") (pin "P$4") (pinfunction "P$4_P$4") (pintype "bidirectional"))
    )
    (net (code "15") (name "B-_STEP") (class "Default")
      (node (ref "U$2") (pin "B-") (pinfunction "B-_B-") (pintype "bidirectional"))
      (node (ref "U$5") (pin "P$7") (pinfunction "P$7_P$7") (pintype "bidirectional"))
    )
    (net (code "16") (name "CCW") (class "Default")
      (node (ref "IC2") (pin "18") (pinfunction "PH6(OC2B)_18") (pintype "bidirectional"))
      (node (ref "U$2") (pin "SW") (pinfunction "SW_SW") (pintype "input"))
    )
    (net (code "17") (name "COMM_1") (class "Default")
      (node (ref "K1") (pin "P") (pinfunction "P_P") (pintype "passive"))
      (node (ref "U$4") (pin "P$9") (pinfunction "P$8_P$9") (pintype "bidirectional"))
    )
    (net (code "18") (name "COMM_2") (class "Default")
      (node (ref "K6") (pin "P") (pinfunction "P_P") (pintype "passive"))
      (node (ref "U$4") (pin "P$8") (pinfunction "P$7_P$8") (pintype "bidirectional"))
    )
    (net (code "19") (name "COMM_3") (class "Default")
      (node (ref "K2") (pin "P") (pinfunction "P_P") (pintype "passive"))
      (node (ref "U$4") (pin "P$7") (pinfunction "P$6_P$7") (pintype "bidirectional"))
    )
    (net (code "20") (name "COMM_4") (class "Default")
      (node (ref "K3") (pin "P") (pinfunction "P_P") (pintype "passive"))
      (node (ref "U$4") (pin "P$6") (pinfunction "P$5_P$6") (pintype "bidirectional"))
    )
    (net (code "21") (name "CS") (class "Default")
      (node (ref "IC2") (pin "19") (pinfunction "(SS/PCINT0)PB0_19") (pintype "bidirectional"))
      (node (ref "IC3") (pin "10") (pinfunction "OE_10") (pintype "input"))
      (node (ref "R16") (pin "2") (pinfunction "2_2") (pintype "passive"))
    )
    (net (code "22") (name "CS_M") (class "Default")
      (node (ref "IC2") (pin "23") (pinfunction "(OC2A/PCINT4)PB4_23") (pintype "bidirectional"))
      (node (ref "U$2") (pin "A2-CS") (pinfunction "A2/CS_A2-CS") (pintype "bidirectional"))
    )
    (net (code "23") (name "D+") (class "Default")
      (node (ref "IC7") (pin "15") (pinfunction "USBDP_15") (pintype "bidirectional"))
      (node (ref "USB") (pin "D+") (pinfunction "D+_D+") (pintype "bidirectional"))
    )
    (net (code "24") (name "D-") (class "Default")
      (node (ref "IC7") (pin "16") (pinfunction "USBDM_16") (pintype "bidirectional"))
      (node (ref "USB") (pin "D-") (pinfunction "D-_D-") (pintype "bidirectional"))
    )
    (net (code "25") (name "D1") (class "Default")
      (node (ref "IC2") (pin "56") (pinfunction "(A11)PC3_56") (pintype "bidirectional"))
      (node (ref "OC1") (pin "16") (pinfunction "COL_16") (pintype "passive"))
      (node (ref "R44") (pin "1") (pinfunction "1_1") (pintype "passive"))
    )
    (net (code "26") (name "D2") (class "Default")
      (node (ref "IC2") (pin "57") (pinfunction "(A12)PC4_57") (pintype "bidirectional"))
      (node (ref "OC1") (pin "14") (pinfunction "COL_14") (pintype "passive"))
      (node (ref "R45") (pin "1") (pinfunction "1_1") (pintype "passive"))
    )
    (net (code "27") (name "D3") (class "Default")
      (node (ref "IC2") (pin "58") (pinfunction "(A13)PC5_58") (pintype "bidirectional"))
      (node (ref "OC1") (pin "12") (pinfunction "COL_12") (pintype "passive"))
      (node (ref "R46") (pin "1") (pinfunction "1_1") (pintype "passive"))
    )
    (net (code "28") (name "D4") (class "Default")
      (node (ref "IC2") (pin "59") (pinfunction "(A14)PC6_59") (pintype "bidirectional"))
      (node (ref "OC1") (pin "10") (pinfunction "COL_10") (pintype "passive"))
      (node (ref "R47") (pin "1") (pinfunction "1_1") (pintype "passive"))
    )
    (net (code "29") (name "DIG1_48V") (class "Default")
      (node (ref "K1") (pin "S") (pinfunction "S_S") (pintype "passive"))
      (node (ref "U$4") (pin "P$5") (pinfunction "P$4_P$5") (pintype "bidirectional"))
    )
    (net (code "30") (name "DIG2_48V") (class "Default")
      (node (ref "K6") (pin "S") (pinfunction "S_S") (pintype "passive"))
      (node (ref "U$4") (pin "P$4") (pinfunction "P$3_P$4") (pintype "bidirectional"))
    )
    (net (code "31") (name "DIG3_48V") (class "Default")
      (node (ref "K2") (pin "S") (pinfunction "S_S") (pintype "passive"))
      (node (ref "U$4") (pin "P$3") (pinfunction "P$2_P$3") (pintype "bidirectional"))
    )
    (net (code "32") (name "DIG4_48V") (class "Default")
      (node (ref "K3") (pin "S") (pinfunction "S_S") (pintype "passive"))
      (node (ref "U$4") (pin "P$2") (pinfunction "P$1_P$2") (pintype "bidirectional"))
    )
    (net (code "33") (name "DIG_24V_IN_1") (class "Default")
      (node (ref "R48") (pin "1") (pinfunction "1_1") (pintype "passive"))
      (node (ref "U$5") (pin "P$13") (pinfunction "P$13_P$13") (pintype "bidirectional"))
    )
    (net (code "34") (name "DIG_24V_IN_2") (class "Default")
      (node (ref "R49") (pin "1") (pinfunction "1_1") (pintype "passive"))
      (node (ref "U$5") (pin "P$14") (pinfunction "P$14_P$14") (pintype "bidirectional"))
    )
    (net (code "35") (name "DIG_24V_IN_3") (class "Default")
      (node (ref "R50") (pin "1") (pinfunction "1_1") (pintype "passive"))
      (node (ref "U$5") (pin "P$15") (pinfunction "P$15_P$15") (pintype "bidirectional"))
    )
    (net (code "36") (name "DIG_24V_IN_4") (class "Default")
      (node (ref "R51") (pin "1") (pinfunction "1_1") (pintype "passive"))
      (node (ref "U$5") (pin "P$16") (pinfunction "P$16_P$16") (pintype "bidirectional"))
    )
    (net (code "37") (name "DTR") (class "Default")
      (node (ref "C29") (pin "1") (pinfunction "1_1") (pintype "passive"))
      (node (ref "IC7") (pin "2") (pinfunction "DTR_2") (pintype "output"))
    )
    (net (code "38") (name "GND") (class "Default")
      (node (ref "ADJUST_OVLO") (pin "2") (pinfunction "2_2") (pintype "passive"))
      (node (ref "ADJUST_UVLO") (pin "2") (pinfunction "2_2") (pintype "passive"))
      (node (ref "C1") (pin "2") (pinfunction "2_2") (pintype "passive"))
      (node (ref "C10") (pin "2") (pinfunction "2_2") (pintype "passive"))
      (node (ref "C11") (pin "-") (pinfunction "-_-") (pintype "passive"))
      (node (ref "C12") (pin "2") (pinfunction "2_2") (pintype "passive"))
      (node (ref "C13") (pin "1") (pinfunction "1_1") (pintype "passive"))
      (node (ref "C14") (pin "2") (pinfunction "2_2") (pintype "passive"))
      (node (ref "C15") (pin "2") (pinfunction "2_2") (pintype "passive"))
      (node (ref "C16") (pin "2") (pinfunction "2_2") (pintype "passive"))
      (node (ref "C17") (pin "2") (pinfunction "2_2") (pintype "passive"))
      (node (ref "C18") (pin "2") (pinfunction "2_2") (pintype "passive"))
      (node (ref "C19") (pin "1") (pinfunction "1_1") (pintype "passive"))
      (node (ref "C2") (pin "2") (pinfunction "2_2") (pintype "passive"))
      (node (ref "C20") (pin "2") (pinfunction "2_2") (pintype "passive"))
      (node (ref "C21") (pin "2") (pinfunction "2_2") (pintype "passive"))
      (node (ref "C25") (pin "2") (pinfunction "2_2") (pintype "passive"))
      (node (ref "C3") (pin "2") (pinfunction "2_2") (pintype "passive"))
      (node (ref "C39") (pin "2") (pinfunction "2_2") (pintype "passive"))
      (node (ref "C4") (pin "2") (pinfunction "2_2") (pintype "passive"))
      (node (ref "C47") (pin "-") (pinfunction "-_-") (pintype "passive"))
      (node (ref "C5") (pin "2") (pinfunction "2_2") (pintype "passive"))
      (node (ref "C6") (pin "2") (pinfunction "2_2") (pintype "passive"))
      (node (ref "C7") (pin "2") (pinfunction "2_2") (pintype "passive"))
      (node (ref "C8") (pin "1") (pinfunction "1_1") (pintype "passive"))
      (node (ref "C9") (pin "2") (pinfunction "2_2") (pintype "passive"))
      (node (ref "D3") (pin "A") (pinfunction "A_A") (pintype "passive"))
      (node (ref "DC2DC_1") (pin "2") (pinfunction "GND_2") (pintype "power_in"))
      (node (ref "IC2") (pin "11") (pinfunction "GND_11") (pintype "power_in"))
      (node (ref "IC2") (pin "32") (pinfunction "GND1_32") (pintype "power_in"))
      (node (ref "IC2") (pin "62") (pinfunction "GND2_62") (pintype "power_in"))
      (node (ref "IC2") (pin "81") (pinfunction "GND3_81") (pintype "power_in"))
      (node (ref "IC2") (pin "99") (pinfunction "AGND_99") (pintype "power_in"))
      (node (ref "IC3") (pin "13") (pinfunction "OE_13") (pintype "input"))
      (node (ref "IC3") (pin "7") (pinfunction "GND_7") (pintype "power_in"))
      (node (ref "IC7") (pin "18") (pinfunction "GND18_18") (pintype "power_in"))
      (node (ref "IC7") (pin "21") (pinfunction "GND21_21") (pintype "power_in"))
      (node (ref "IC7") (pin "25") (pinfunction "AGND_25") (pintype "power_in"))
      (node (ref "IC7") (pin "26") (pinfunction "TEST_26") (pintype "input"))
      (node (ref "IC7") (pin "7") (pinfunction "GND7_7") (pintype "power_in"))
      (node (ref "K1") (pin "2") (pinfunction "2_2") (pintype "passive"))
      (node (ref "K2") (pin "2") (pinfunction "2_2") (pintype "passive"))
      (node (ref "K3") (pin "2") (pinfunction "2_2") (pintype "passive"))
      (node (ref "K6") (pin "2") (pinfunction "2_2") (pintype "passive"))
      (node (ref "OC1") (pin "11") (pinfunction "EMIT_11") (pintype "passive"))
      (node (ref "OC1") (pin "13") (pinfunction "EMIT_13") (pintype "passive"))
      (node (ref "OC1") (pin "15") (pinfunction "EMIT_15") (pintype "passive"))
      (node (ref "OC1") (pin "9") (pinfunction "EMIT_9") (pintype "passive"))
      (node (ref "PFET-M") (pin "1") (pinfunction "G_1") (pintype "passive"))
      (node (ref "Q1") (pin "3") (pinfunction "E_3") (pintype "passive"))
      (node (ref "Q2") (pin "3") (pinfunction "E_3") (pintype "passive"))
      (node (ref "R18") (pin "1") (pinfunction "1_1") (pintype "passive"))
      (node (ref "R19") (pin "1") (pinfunction "1_1") (pintype "passive"))
      (node (ref "R38") (pin "2") (pinfunction "2_2") (pintype "passive"))
      (node (ref "R39") (pin "2") (pinfunction "2_2") (pintype "passive"))
      (node (ref "R4") (pin "1") (pinfunction "1_1") (pintype "passive"))
      (node (ref "R40") (pin "1") (pinfunction "1_1") (pintype "passive"))
      (node (ref "R41") (pin "1") (pinfunction "1_1") (pintype "passive"))
      (node (ref "SW1") (pin "8") (pinfunction "8_8") (pintype "passive"))
      (node (ref "U$1") (pin "3") (pinfunction "GND_3") (pintype "power_in"))
      (node (ref "U$2") (pin "GND@0") (pinfunction "GND_GND@0") (pintype "power_in"))
      (node (ref "U$2") (pin "GND@1") (pinfunction "GND_GND@1") (pintype "power_in"))
      (node (ref "U$2") (pin "GND@2") (pinfunction "GND_GND@2") (pintype "power_in"))
      (node (ref "U$2") (pin "GND@3") (pinfunction "GND_GND@3") (pintype "power_in"))
      (node (ref "U$37") (pin "GND") (pinfunction "GND_GND") (pintype "bidirectional"))
      (node (ref "U$37") (pin "HVEN") (pinfunction "HVEN_HVEN") (pintype "bidirectional"))
      (node (ref "U$38") (pin "2") (pinfunction "P$1_2") (pintype "bidirectional"))
      (node (ref "U$39") (pin "A") (pinfunction "P$1_A") (pintype "bidirectional"))
      (node (ref "U$4") (pin "P$11") (pinfunction "P$10_P$11") (pintype "bidirectional"))
      (node (ref "U$40") (pin "3") (pinfunction "GND_3") (pintype "bidirectional"))
      (node (ref "U$41") (pin "P$1") (pinfunction "P$2_P$1") (pintype "bidirectional"))
      (node (ref "U$42") (pin "P$1") (pinfunction "P$2_P$1") (pintype "bidirectional"))
      (node (ref "U$5") (pin "P$5") (pinfunction "P$5_P$5") (pintype "bidirectional"))
      (node (ref "U1") (pin "2") (pinfunction "GND_2") (pintype "input"))
      (node (ref "U1") (pin "4") (pinfunction "GND_4") (pintype "input"))
      (node (ref "U2") (pin "8") (pinfunction "SH_8") (pintype "input"))
      (node (ref "U2") (pin "D2") (pinfunction "D2_D2") (pintype "input"))
      (node (ref "U2") (pin "D4") (pinfunction "D4_D4") (pintype "input"))
      (node (ref "U2") (pin "M1") (pinfunction "SH_M1") (pintype "input"))
      (node (ref "U2") (pin "M2") (pinfunction "SH_M2") (pintype "input"))
      (node (ref "U3") (pin "11") (pinfunction "VSSRX_11") (pintype "power_in"))
      (node (ref "U3") (pin "18") (pinfunction "VSSTX_18") (pintype "power_in"))
      (node (ref "U3") (pin "2") (pinfunction "VSS_2") (pintype "power_in"))
      (node (ref "U3") (pin "21") (pinfunction "VSSPLL_21") (pintype "power_in"))
      (node (ref "U3") (pin "22") (pinfunction "VSSOSC_22") (pintype "power_in"))
      (node (ref "USB") (pin "GND") (pinfunction "GND_GND") (pintype "bidirectional"))
      (node (ref "Y1") (pin "2") (pinfunction "2_2") (pintype "passive"))
      (node (ref "Y2") (pin "2") (pinfunction "GND_2") (pintype "passive"))
      (node (ref "Y2") (pin "4") (pinfunction "GND_4") (pintype "passive"))
    )
    (net (code "39") (name "INT") (class "Default")
      (node (ref "IC2") (pin "7") (pinfunction "(OC3C/INT5)PE5_7") (pintype "bidirectional"))
      (node (ref "IC3") (pin "11") (pinfunction "O_11") (pintype "tri_state"))
    )
    (net (code "40") (name "INT_3V3") (class "Default")
      (node (ref "IC3") (pin "12") (pinfunction "I_12") (pintype "input"))
      (node (ref "U3") (pin "4") (pinfunction "INT_4") (pintype "output"))
    )
    (net (code "41") (name "LED1") (class "Default")
      (node (ref "U2") (pin "D1") (pinfunction "D1_D1") (pintype "input"))
      (node (ref "U3") (pin "27") (pinfunction "LEDA_27") (pintype "output"))
    )
    (net (code "42") (name "LED2") (class "Default")
      (node (ref "U2") (pin "D3") (pinfunction "D3_D3") (pintype "input"))
      (node (ref "U3") (pin "26") (pinfunction "LEDB_26") (pintype "output"))
    )
    (net (code "43") (name "MISO_1") (class "Default")
      (node (ref "IC2") (pin "22") (pinfunction "(MISO/PCINT3)PB3_22") (pintype "bidirectional"))
      (node (ref "IC3") (pin "8") (pinfunction "O_8") (pintype "tri_state"))
      (node (ref "U$2") (pin "D12-MISO") (pinfunction "D12/MISO_D12-MISO") (pintype "bidirectional"))
    )
    (net (code "44") (name "MOSI_1") (class "Default")
      (node (ref "IC2") (pin "21") (pinfunction "(MOSI/PCINT2)PB2_21") (pintype "bidirectional"))
      (node (ref "R14") (pin "2") (pinfunction "2_2") (pintype "passive"))
      (node (ref "U$2") (pin "D11-MOSI") (pinfunction "D11/MOSI_D11-MOSI") (pintype "bidirectional"))
    )
    (net (code "45") (name "Net-(C25-Pad1)") (class "Default")
      (node (ref "C25") (pin "1") (pinfunction "1_1") (pintype "passive"))
      (node (ref "R24") (pin "1") (pinfunction "1_1") (pintype "passive"))
      (node (ref "R31") (pin "1") (pinfunction "1_1") (pintype "passive"))
      (node (ref "R32") (pin "1") (pinfunction "1_1") (pintype "passive"))
      (node (ref "R37") (pin "1") (pinfunction "1_1") (pintype "passive"))
    )
    (net (code "46") (name "Net-(IC2-RESET)") (class "Default")
      (node (ref "C13") (pin "2") (pinfunction "2_2") (pintype "passive"))
      (node (ref "D2") (pin "A") (pinfunction "A_A") (pintype "passive"))
      (node (ref "IC2") (pin "30") (pinfunction "RESET_30") (pintype "input"))
      (node (ref "R21") (pin "1") (pinfunction "1_1") (pintype "passive"))
    )
    (net (code "47") (name "Net-(IC2-XTAL2)") (class "Default")
      (node (ref "IC2") (pin "33") (pinfunction "XTAL2_33") (pintype "output"))
      (node (ref "R20") (pin "2") (pinfunction "2_2") (pintype "passive"))
      (node (ref "Y1") (pin "1") (pinfunction "1_1") (pintype "passive"))
    )
    (net (code "48") (name "Net-(IC8A-A)") (class "Default")
      (node (ref "IC8") (pin "6") (pinfunction "A_6") (pintype "bidirectional"))
      (node (ref "R1") (pin "1") (pinfunction "1_1") (pintype "passive"))
      (node (ref "R3") (pin "1") (pinfunction "1_1") (pintype "passive"))
    )
    (net (code "49") (name "Net-(IC8A-B)") (class "Default")
      (node (ref "IC8") (pin "7") (pinfunction "B_7") (pintype "bidirectional"))
      (node (ref "R2") (pin "1") (pinfunction "1_1") (pintype "passive"))
      (node (ref "R4") (pin "2") (pinfunction "2_2") (pintype "passive"))
    )
    (net (code "50") (name "Net-(LED1-PadC)") (class "Default")
      (node (ref "LED1") (pin "C") (pinfunction "C_C") (pintype "passive"))
      (node (ref "R6") (pin "2") (pinfunction "2_2") (pintype "passive"))
    )
    (net (code "51") (name "Net-(LED2-PadC)") (class "Default")
      (node (ref "LED2") (pin "C") (pinfunction "C_C") (pintype "passive"))
      (node (ref "R7") (pin "2") (pinfunction "2_2") (pintype "passive"))
    )
    (net (code "52") (name "Net-(OC1A-C)") (class "Default")
      (node (ref "OC1") (pin "2") (pinfunction "C_2") (pintype "passive"))
      (node (ref "R48") (pin "2") (pinfunction "2_2") (pintype "passive"))
    )
    (net (code "53") (name "Net-(OC1B-C)") (class "Default")
      (node (ref "OC1") (pin "4") (pinfunction "C_4") (pintype "passive"))
      (node (ref "R49") (pin "2") (pinfunction "2_2") (pintype "passive"))
    )
    (net (code "54") (name "Net-(OC1C-C)") (class "Default")
      (node (ref "OC1") (pin "6") (pinfunction "C_6") (pintype "passive"))
      (node (ref "R50") (pin "2") (pinfunction "2_2") (pintype "passive"))
    )
    (net (code "55") (name "Net-(OC1D-C)") (class "Default")
      (node (ref "OC1") (pin "8") (pinfunction "C_8") (pintype "passive"))
      (node (ref "R51") (pin "2") (pinfunction "2_2") (pintype "passive"))
    )
    (net (code "56") (name "Net-(PWR-LED1-PadA)") (class "Default")
      (node (ref "PWR-LED1") (pin "A") (pinfunction "A_A") (pintype "passive"))
      (node (ref "R43") (pin "1") (pinfunction "1_1") (pintype "passive"))
    )
    (net (code "57") (name "Net-(Q1-B)") (class "Default")
      (node (ref "Q1") (pin "1") (pinfunction "B_1") (pintype "passive"))
      (node (ref "R8") (pin "1") (pinfunction "1_1") (pintype "passive"))
    )
    (net (code "58") (name "Net-(Q1-C)") (class "Default")
      (node (ref "Q1") (pin "2") (pinfunction "C_2") (pintype "passive"))
      (node (ref "R6") (pin "1") (pinfunction "1_1") (pintype "passive"))
    )
    (net (code "59") (name "Net-(Q2-B)") (class "Default")
      (node (ref "Q2") (pin "1") (pinfunction "B_1") (pintype "passive"))
      (node (ref "R9") (pin "1") (pinfunction "1_1") (pintype "passive"))
    )
    (net (code "60") (name "Net-(Q2-C)") (class "Default")
      (node (ref "Q2") (pin "2") (pinfunction "C_2") (pintype "passive"))
      (node (ref "R7") (pin "1") (pinfunction "1_1") (pintype "passive"))
    )
    (net (code "61") (name "Net-(R30-Pad2)") (class "Default")
      (node (ref "R30") (pin "2") (pinfunction "2_2") (pintype "passive"))
      (node (ref "TX") (pin "A") (pinfunction "A_A") (pintype "passive"))
    )
    (net (code "62") (name "Net-(R33-Pad2)") (class "Default")
      (node (ref "R33") (pin "2") (pinfunction "2_2") (pintype "passive"))
      (node (ref "RX") (pin "A") (pinfunction "A_A") (pintype "passive"))
    )
    (net (code "63") (name "Net-(U$1-ADDR)") (class "Default")
      (node (ref "SW1") (pin "1") (pinfunction "1_1") (pintype "passive"))
      (node (ref "SW1") (pin "2") (pinfunction "2_2") (pintype "passive"))
      (node (ref "SW1") (pin "3") (pinfunction "3_3") (pintype "passive"))
      (node (ref "SW1") (pin "4") (pinfunction "4_4") (pintype "passive"))
      (node (ref "U$1") (pin "1") (pinfunction "ADDR_1") (pintype "input"))
    )
    (net (code "64") (name "Net-(U$1-AIN0)") (class "Default")
      (node (ref "R35") (pin "1") (pinfunction "1_1") (pintype "passive"))
      (node (ref "U$1") (pin "4") (pinfunction "AIN0_4") (pintype "input"))
    )
    (net (code "65") (name "Net-(U$1-AIN1)") (class "Default")
      (node (ref "R34") (pin "1") (pinfunction "1_1") (pintype "passive"))
      (node (ref "U$1") (pin "5") (pinfunction "AIN1_5") (pintype "input"))
    )
    (net (code "66") (name "Net-(U$1-AIN2)") (class "Default")
      (node (ref "R36") (pin "2") (pinfunction "2_2") (pintype "passive"))
      (node (ref "U$1") (pin "6") (pinfunction "AIN2_6") (pintype "input"))
    )
    (net (code "67") (name "Net-(U$1-AIN3)") (class "Default")
      (node (ref "R29") (pin "1") (pinfunction "1_1") (pintype "passive"))
      (node (ref "U$1") (pin "7") (pinfunction "AIN3_7") (pintype "power_in"))
    )
    (net (code "68") (name "Net-(U$1-ALERT{slash}RDY)") (class "Default")
      (node (ref "R28") (pin "2") (pinfunction "2_2") (pintype "passive"))
      (node (ref "U$1") (pin "2") (pinfunction "ALERT/RDY_2") (pintype "power_in"))
    )
    (net (code "69") (name "Net-(U$40-A1)") (class "Default")
      (node (ref "R42") (pin "2") (pinfunction "2_2") (pintype "passive"))
      (node (ref "U$37") (pin "FLAG") (pinfunction "FLAG_FLAG") (pintype "bidirectional"))
      (node (ref "U$40") (pin "1") (pinfunction "A1_1") (pintype "bidirectional"))
    )
    (net (code "70") (name "Net-(U$40-A2)") (class "Default")
      (node (ref "R39") (pin "1") (pinfunction "1_1") (pintype "passive"))
      (node (ref "U$40") (pin "2") (pinfunction "A2_2") (pintype "bidirectional"))
    )
    (net (code "71") (name "Net-(U$40-Y1)") (class "Default")
      (node (ref "PWR-LED1") (pin "C") (pinfunction "C_C") (pintype "passive"))
      (node (ref "U$40") (pin "5") (pinfunction "Y1_5") (pintype "bidirectional"))
    )
    (net (code "72") (name "Net-(U$40-Y2)") (class "Default")
      (node (ref "R15_BYPASS8") (pin "2") (pinfunction "2_2") (pintype "passive"))
      (node (ref "U$40") (pin "6") (pinfunction "Y2_6") (pintype "bidirectional"))
    )
    (net (code "73") (name "Net-(U2-CT1)") (class "Default")
      (node (ref "C39") (pin "1") (pinfunction "1_1") (pintype "passive"))
      (node (ref "L1") (pin "1") (pinfunction "1_1") (pintype "passive"))
      (node (ref "R10") (pin "2") (pinfunction "2_2") (pintype "passive"))
      (node (ref "R12") (pin "2") (pinfunction "2_2") (pintype "passive"))
      (node (ref "R17") (pin "2") (pinfunction "2_2") (pintype "passive"))
      (node (ref "R23") (pin "2") (pinfunction "2_2") (pintype "passive"))
      (node (ref "U2") (pin "4") (pinfunction "CT1_4") (pintype "input"))
    )
    (net (code "74") (name "Net-(U3-CS)") (class "Default")
      (node (ref "R13") (pin "1") (pinfunction "1_1") (pintype "passive"))
      (node (ref "R16") (pin "1") (pinfunction "1_1") (pintype "passive"))
      (node (ref "U3") (pin "9") (pinfunction "CS_9") (pintype "input"))
    )
    (net (code "75") (name "Net-(U3-OSC1)") (class "Default")
      (node (ref "C10") (pin "1") (pinfunction "1_1") (pintype "passive"))
      (node (ref "U3") (pin "23") (pinfunction "OSC1_23") (pintype "input"))
      (node (ref "Y2") (pin "3") (pinfunction "C2_3") (pintype "passive"))
    )
    (net (code "76") (name "Net-(U3-OSC2)") (class "Default")
      (node (ref "C14") (pin "1") (pinfunction "1_1") (pintype "passive"))
      (node (ref "U3") (pin "24") (pinfunction "OSC2_24") (pintype "output"))
      (node (ref "Y2") (pin "1") (pinfunction "C1_1") (pintype "passive"))
    )
    (net (code "77") (name "Net-(U3-RBIAS)") (class "Default")
      (node (ref "R18") (pin "2") (pinfunction "2_2") (pintype "passive"))
      (node (ref "R19") (pin "2") (pinfunction "2_2") (pintype "passive"))
      (node (ref "U3") (pin "14") (pinfunction "RBIAS_14") (pintype "passive"))
    )
    (net (code "78") (name "Net-(U3-RESET)") (class "Default")
      (node (ref "R11") (pin "1") (pinfunction "1_1") (pintype "passive"))
      (node (ref "U3") (pin "10") (pinfunction "RESET_10") (pintype "input"))
    )
    (net (code "79") (name "Net-(U3-SCK)") (class "Default")
      (node (ref "R15") (pin "1") (pinfunction "1_1") (pintype "passive"))
      (node (ref "U3") (pin "8") (pinfunction "SCK_8") (pintype "input"))
    )
    (net (code "80") (name "Net-(U3-SI)") (class "Default")
      (node (ref "R14") (pin "1") (pinfunction "1_1") (pintype "passive"))
      (node (ref "U3") (pin "7") (pinfunction "SI_7") (pintype "input"))
    )
    (net (code "81") (name "Net-(U3-VCAP)") (class "Default")
      (node (ref "C8") (pin "2") (pinfunction "2_2") (pintype "passive"))
      (node (ref "U3") (pin "1") (pinfunction "VCAP_1") (pintype "power_in"))
    )
    (net (code "82") (name "OVLO") (class "Default")
      (node (ref "ADJUST_OVLO") (pin "1") (pinfunction "1_1") (pintype "passive"))
      (node (ref "R26") (pin "2") (pinfunction "2_2") (pintype "passive"))
      (node (ref "U$37") (pin "OVLO") (pinfunction "OVLO_OVLO") (pintype "bidirectional"))
    )
    (net (code "83") (name "RELAY_1_IN") (class "Default")
      (node (ref "IC2") (pin "35") (pinfunction "PL0(ICP4)_35") (pintype "bidirectional"))
      (node (ref "K1") (pin "1") (pinfunction "1_1") (pintype "passive"))
    )
    (net (code "84") (name "RELAY_2_IN") (class "Default")
      (node (ref "IC2") (pin "36") (pinfunction "PL1(ICP5)_36") (pintype "bidirectional"))
      (node (ref "K6") (pin "1") (pinfunction "1_1") (pintype "passive"))
    )
    (net (code "85") (name "RELAY_3_IN") (class "Default")
      (node (ref "IC2") (pin "37") (pinfunction "PL2(T5)_37") (pintype "bidirectional"))
      (node (ref "K2") (pin "1") (pinfunction "1_1") (pintype "passive"))
    )
    (net (code "86") (name "RELAY_4_IN") (class "Default")
      (node (ref "IC2") (pin "38") (pinfunction "PL3(OC5A)_38") (pintype "bidirectional"))
      (node (ref "K3") (pin "1") (pinfunction "1_1") (pintype "passive"))
    )
    (net (code "87") (name "RESET_1") (class "Default")
      (node (ref "IC2") (pin "63") (pinfunction "PJ0(RXD3/PCINT9)_63") (pintype "bidirectional"))
      (node (ref "U$2") (pin "D8-RESET") (pinfunction "D8/RESET_D8-RESET") (pintype "bidirectional"))
    )
    (net (code "88") (name "RESET_FTDI") (class "Default")
      (node (ref "C29") (pin "2") (pinfunction "2_2") (pintype "passive"))
      (node (ref "IC2") (pin "5") (pinfunction "(OC3A/AIN1)PE3_5") (pintype "bidirectional"))
    )
    (net (code "89") (name "RE{slash}DE_MAX") (class "Default")
      (node (ref "IC2") (pin "50") (pinfunction "(T0)PD7_50") (pintype "bidirectional"))
      (node (ref "IC8") (pin "2") (pinfunction "~{RE}_2") (pintype "input"))
      (node (ref "IC8") (pin "3") (pinfunction "DE_3") (pintype "input"))
    )
    (net (code "90") (name "RXL") (class "Default")
      (node (ref "IC7") (pin "23") (pinfunction "TXLED_23") (pintype "input"))
      (node (ref "RX") (pin "C") (pinfunction "C_C") (pintype "passive"))
    )
    (net (code "91") (name "RX_FTDI") (class "Default")
      (node (ref "IC2") (pin "2") (pinfunction "(RXD0/PCIN8)PE0_2") (pintype "bidirectional"))
      (node (ref "IC7") (pin "1") (pinfunction "TXD_1") (pintype "output"))
    )
    (net (code "92") (name "RX_MAX") (class "Default")
      (node (ref "IC2") (pin "45") (pinfunction "(RXD1/INT2)PD2_45") (pintype "bidirectional"))
      (node (ref "IC8") (pin "1") (pinfunction "R_1") (pintype "output"))
      (node (ref "R8") (pin "2") (pinfunction "2_2") (pintype "passive"))
    )
    (net (code "93") (name "SCK_1") (class "Default")
      (node (ref "IC2") (pin "20") (pinfunction "(SCK/PCINT1)PB1_20") (pintype "bidirectional"))
      (node (ref "R15") (pin "2") (pinfunction "2_2") (pintype "passive"))
      (node (ref "U$2") (pin "D13-SCK") (pinfunction "D13/SCK_D13-SCK") (pintype "bidirectional"))
    )
    (net (code "94") (name "SCL_ADC") (class "Default")
      (node (ref "IC2") (pin "43") (pinfunction "(SCL/INT0)PD0_43") (pintype "bidirectional"))
      (node (ref "R22") (pin "1") (pinfunction "1_1") (pintype "passive"))
      (node (ref "SW1") (pin "6") (pinfunction "6_6") (pintype "passive"))
      (node (ref "U$1") (pin "10") (pinfunction "SCL_10") (pintype "input"))
    )
    (net (code "95") (name "SDA_ADC") (class "Default")
      (node (ref "IC2") (pin "44") (pinfunction "(SDA/INT1)PD1_44") (pintype "bidirectional"))
      (node (ref "R25") (pin "1") (pinfunction "1_1") (pintype "passive"))
      (node (ref "SW1") (pin "5") (pinfunction "5_5") (pintype "passive"))
      (node (ref "U$1") (pin "9") (pinfunction "SDA_9") (pintype "bidirectional"))
    )
    (net (code "96") (name "SETI") (class "Default")
      (node (ref "R38") (pin "1") (pinfunction "1_1") (pintype "passive"))
      (node (ref "U$37") (pin "SETI") (pinfunction "SETI_SETI") (pintype "bidirectional"))
    )
    (net (code "97") (name "SO_3V3") (class "Default")
      (node (ref "IC3") (pin "9") (pinfunction "I_9") (pintype "input"))
      (node (ref "U3") (pin "6") (pinfunction "SO_6") (pintype "output"))
    )
    (net (code "98") (name "TPIN+") (class "Default")
      (node (ref "R32") (pin "2") (pinfunction "2_2") (pintype "passive"))
      (node (ref "R37") (pin "2") (pinfunction "2_2") (pintype "passive"))
      (node (ref "U$7") (pin "C") (pinfunction "2_C") (pintype "bidirectional"))
      (node (ref "U2") (pin "1") (pinfunction "RD+1_1") (pintype "input"))
      (node (ref "U3") (pin "13") (pinfunction "TPIN+_13") (pintype "input"))
    )
    (net (code "99") (name "TPIN-") (class "Default")
      (node (ref "R24") (pin "2") (pinfunction "2_2") (pintype "passive"))
      (node (ref "R31") (pin "2") (pinfunction "2_2") (pintype "passive"))
      (node (ref "U$7") (pin "A") (pinfunction "1_A") (pintype "bidirectional"))
      (node (ref "U2") (pin "2") (pinfunction "RD-1_2") (pintype "input"))
      (node (ref "U3") (pin "12") (pinfunction "TPIN-_12") (pintype "input"))
    )
    (net (code "100") (name "TPOUT+") (class "Default")
      (node (ref "R10") (pin "1") (pinfunction "1_1") (pintype "passive"))
      (node (ref "R12") (pin "1") (pinfunction "1_1") (pintype "passive"))
      (node (ref "U$6") (pin "C") (pinfunction "2_C") (pintype "bidirectional"))
      (node (ref "U2") (pin "5") (pinfunction "TD+1_5") (pintype "input"))
      (node (ref "U3") (pin "17") (pinfunction "TPOUT+_17") (pintype "output"))
    )
    (net (code "101") (name "TPOUT-") (class "Default")
      (node (ref "R17") (pin "1") (pinfunction "1_1") (pintype "passive"))
      (node (ref "R23") (pin "1") (pinfunction "1_1") (pintype "passive"))
      (node (ref "U$6") (pin "A") (pinfunction "1_A") (pintype "bidirectional"))
      (node (ref "U2") (pin "6") (pinfunction "TD-1_6") (pintype "input"))
      (node (ref "U3") (pin "16") (pinfunction "TPOUT-_16") (pintype "output"))
    )
    (net (code "102") (name "TXL") (class "Default")
      (node (ref "IC7") (pin "22") (pinfunction "RXLED_22") (pintype "input"))
      (node (ref "TX") (pin "C") (pinfunction "C_C") (pintype "passive"))
    )
    (net (code "103") (name "TX_FTDI") (class "Default")
      (node (ref "IC2") (pin "3") (pinfunction "(TXD0)PE1_3") (pintype "bidirectional"))
      (node (ref "IC7") (pin "5") (pinfunction "RXD_5") (pintype "input"))
    )
    (net (code "104") (name "TX_MAX") (class "Default")
      (node (ref "IC2") (pin "46") (pinfunction "(TXD1/INT3)PD3_46") (pintype "bidirectional"))
      (node (ref "IC8") (pin "4") (pinfunction "D_4") (pintype "input"))
      (node (ref "R9") (pin "2") (pinfunction "2_2") (pintype "passive"))
    )
    (net (code "105") (name "UVLO") (class "Default")
      (node (ref "ADJUST_UVLO") (pin "1") (pinfunction "1_1") (pintype "passive"))
      (node (ref "R27") (pin "2") (pinfunction "2_2") (pintype "passive"))
      (node (ref "U$37") (pin "UVLO") (pinfunction "UVLO_UVLO") (pintype "bidirectional"))
    )
    (net (code "106") (name "VCC") (class "Default")
      (node (ref "C1") (pin "1") (pinfunction "1_1") (pintype "passive"))
      (node (ref "C11") (pin "+") (pinfunction "+_+") (pintype "passive"))
      (node (ref "C12") (pin "1") (pinfunction "1_1") (pintype "passive"))
      (node (ref "C15") (pin "1") (pinfunction "1_1") (pintype "passive"))
      (node (ref "C2") (pin "1") (pinfunction "1_1") (pintype "passive"))
      (node (ref "C20") (pin "1") (pinfunction "1_1") (pintype "passive"))
      (node (ref "C21") (pin "1") (pinfunction "1_1") (pintype "passive"))
      (node (ref "C3") (pin "1") (pinfunction "1_1") (pintype "passive"))
      (node (ref "C4") (pin "1") (pinfunction "1_1") (pintype "passive"))
      (node (ref "D2") (pin "C") (pinfunction "C_C") (pintype "passive"))
      (node (ref "DC2DC_1") (pin "3") (pinfunction "+5V_3") (pintype "power_in"))
      (node (ref "F1") (pin "1") (pinfunction "1_1") (pintype "passive"))
      (node (ref "IC2") (pin "10") (pinfunction "VCC_10") (pintype "power_in"))
      (node (ref "IC2") (pin "100") (pinfunction "AVCC_100") (pintype "power_in"))
      (node (ref "IC2") (pin "31") (pinfunction "VCC1_31") (pintype "power_in"))
      (node (ref "IC2") (pin "61") (pinfunction "VCC2_61") (pintype "power_in"))
      (node (ref "IC2") (pin "80") (pinfunction "VCC3_80") (pintype "power_in"))
      (node (ref "IC3") (pin "14") (pinfunction "VCC_14") (pintype "power_in"))
      (node (ref "IC7") (pin "19") (pinfunction "RESET_19") (pintype "input"))
      (node (ref "IC7") (pin "20") (pinfunction "VCC_20") (pintype "power_in"))
      (node (ref "IC7") (pin "4") (pinfunction "VCCIO_4") (pintype "power_in"))
      (node (ref "L2") (pin "2") (pinfunction "2_2") (pintype "passive"))
      (node (ref "LED1") (pin "A") (pinfunction "A_A") (pintype "passive"))
      (node (ref "LED2") (pin "A") (pinfunction "A_A") (pintype "passive"))
      (node (ref "R15_BYPASS8") (pin "1") (pinfunction "1_1") (pintype "passive"))
      (node (ref "R21") (pin "2") (pinfunction "2_2") (pintype "passive"))
      (node (ref "R22") (pin "2") (pinfunction "2_2") (pintype "passive"))
      (node (ref "R25") (pin "2") (pinfunction "2_2") (pintype "passive"))
      (node (ref "R28") (pin "1") (pinfunction "1_1") (pintype "passive"))
      (node (ref "R3") (pin "2") (pinfunction "2_2") (pintype "passive"))
      (node (ref "R30") (pin "1") (pinfunction "1_1") (pintype "passive"))
      (node (ref "R33") (pin "1") (pinfunction "1_1") (pintype "passive"))
      (node (ref "R40") (pin "2") (pinfunction "2_2") (pintype "passive"))
      (node (ref "R41") (pin "2") (pinfunction "2_2") (pintype "passive"))
      (node (ref "R42") (pin "1") (pinfunction "1_1") (pintype "passive"))
      (node (ref "R43") (pin "2") (pinfunction "2_2") (pintype "passive"))
      (node (ref "R44") (pin "2") (pinfunction "2_2") (pintype "passive"))
      (node (ref "R45") (pin "2") (pinfunction "2_2") (pintype "passive"))
      (node (ref "R46") (pin "2") (pinfunction "2_2") (pintype "passive"))
      (node (ref "R47") (pin "2") (pinfunction "2_2") (pintype "passive"))
      (node (ref "SW1") (pin "7") (pinfunction "7_7") (pintype "passive"))
      (node (ref "U$37") (pin "EN") (pinfunction "EN_EN") (pintype "bidirectional"))
      (node (ref "U$37") (pin "RIEN") (pinfunction "RIEN_RIEN") (pintype "bidirectional"))
      (node (ref "U$40") (pin "4") (pinfunction "VCC_4") (pintype "bidirectional"))
      (node (ref "U1") (pin "1") (pinfunction "IN_1") (pintype "input"))
    )
    (net (code "107") (name "VDD_IC") (class "Default")
      (node (ref "C16") (pin "1") (pinfunction "1_1") (pintype "passive"))
      (node (ref "L2") (pin "1") (pinfunction "1_1") (pintype "passive"))
      (node (ref "U$1") (pin "8") (pinfunction "VDD_8") (pintype "output"))
    )
    (net (code "108") (name "VMOT") (class "Default")
      (node (ref "U$2") (pin "VS+") (pinfunction "VMOT_VS+") (pintype "power_in"))
      (node (ref "U$5") (pin "P$6") (pinfunction "P$6_P$6") (pintype "bidirectional"))
    )
    (net (code "109") (name "XTAL1") (class "Default")
      (node (ref "IC2") (pin "34") (pinfunction "XTAL1_34") (pintype "input"))
      (node (ref "R20") (pin "1") (pinfunction "1_1") (pintype "passive"))
      (node (ref "Y1") (pin "3") (pinfunction "3_3") (pintype "passive"))
    )
    (net (code "110") (name "XVCC") (class "Default")
      (node (ref "F1") (pin "2") (pinfunction "2_2") (pintype "passive"))
      (node (ref "USB") (pin "VBUS") (pinfunction "VBUS_VBUS") (pintype "bidirectional"))
    )
    (net (code "111") (name "unconnected-(IC2-(A8)PC0-Pad53)") (class "Default")
      (node (ref "IC2") (pin "53") (pinfunction "(A8)PC0_53") (pintype "bidirectional"))
    )
    (net (code "112") (name "unconnected-(IC2-(A9)PC1-Pad54)") (class "Default")
      (node (ref "IC2") (pin "54") (pinfunction "(A9)PC1_54") (pintype "bidirectional"))
    )
    (net (code "113") (name "unconnected-(IC2-(A10)PC2-Pad55)") (class "Default")
      (node (ref "IC2") (pin "55") (pinfunction "(A10)PC2_55") (pintype "bidirectional"))
    )
    (net (code "114") (name "unconnected-(IC2-(A15)PC7-Pad60)") (class "Default")
      (node (ref "IC2") (pin "60") (pinfunction "(A15)PC7_60") (pintype "bidirectional"))
    )
    (net (code "115") (name "unconnected-(IC2-(AD0)PA0-Pad78)") (class "Default")
      (node (ref "IC2") (pin "78") (pinfunction "(AD0)PA0_78") (pintype "bidirectional"))
    )
    (net (code "116") (name "unconnected-(IC2-(AD1)PA1-Pad77)") (class "Default")
      (node (ref "IC2") (pin "77") (pinfunction "(AD1)PA1_77") (pintype "bidirectional"))
    )
    (net (code "117") (name "unconnected-(IC2-(AD2)PA2-Pad76)") (class "Default")
      (node (ref "IC2") (pin "76") (pinfunction "(AD2)PA2_76") (pintype "bidirectional"))
    )
    (net (code "118") (name "unconnected-(IC2-(AD3)PA3-Pad75)") (class "Default")
      (node (ref "IC2") (pin "75") (pinfunction "(AD3)PA3_75") (pintype "bidirectional"))
    )
    (net (code "119") (name "unconnected-(IC2-(AD4)PA4-Pad74)") (class "Default")
      (node (ref "IC2") (pin "74") (pinfunction "(AD4)PA4_74") (pintype "bidirectional"))
    )
    (net (code "120") (name "unconnected-(IC2-(AD5)PA5-Pad73)") (class "Default")
      (node (ref "IC2") (pin "73") (pinfunction "(AD5)PA5_73") (pintype "bidirectional"))
    )
    (net (code "121") (name "unconnected-(IC2-(AD6)PA6-Pad72)") (class "Default")
      (node (ref "IC2") (pin "72") (pinfunction "(AD6)PA6_72") (pintype "bidirectional"))
    )
    (net (code "122") (name "unconnected-(IC2-(AD7)PA7-Pad71)") (class "Default")
      (node (ref "IC2") (pin "71") (pinfunction "(AD7)PA7_71") (pintype "bidirectional"))
    )
    (net (code "123") (name "unconnected-(IC2-(ADC0)PF0-Pad97)") (class "Default")
      (node (ref "IC2") (pin "97") (pinfunction "(ADC0)PF0_97") (pintype "bidirectional"))
    )
    (net (code "124") (name "unconnected-(IC2-(ADC1)PF1-Pad96)") (class "Default")
      (node (ref "IC2") (pin "96") (pinfunction "(ADC1)PF1_96") (pintype "bidirectional"))
    )
    (net (code "125") (name "unconnected-(IC2-(ADC2)PF2-Pad95)") (class "Default")
      (node (ref "IC2") (pin "95") (pinfunction "(ADC2)PF2_95") (pintype "bidirectional"))
    )
    (net (code "126") (name "unconnected-(IC2-(ADC3)PF3-Pad94)") (class "Default")
      (node (ref "IC2") (pin "94") (pinfunction "(ADC3)PF3_94") (pintype "bidirectional"))
    )
    (net (code "127") (name "unconnected-(IC2-(ADC4{slash}TCK)PF4-Pad93)") (class "Default")
      (node (ref "IC2") (pin "93") (pinfunction "(ADC4/TCK)PF4_93") (pintype "bidirectional"))
    )
    (net (code "128") (name "unconnected-(IC2-(ADC5{slash}TMS)PF5-Pad92)") (class "Default")
      (node (ref "IC2") (pin "92") (pinfunction "(ADC5/TMS)PF5_92") (pintype "bidirectional"))
    )
    (net (code "129") (name "unconnected-(IC2-(ADC6{slash}TDO)PF6-Pad91)") (class "Default")
      (node (ref "IC2") (pin "91") (pinfunction "(ADC6/TDO)PF6_91") (pintype "bidirectional"))
    )
    (net (code "130") (name "unconnected-(IC2-(ADC7{slash}TDI)PF7-Pad90)") (class "Default")
      (node (ref "IC2") (pin "90") (pinfunction "(ADC7/TDI)PF7_90") (pintype "bidirectional"))
    )
    (net (code "131") (name "unconnected-(IC2-(ALE)PG2-Pad70)") (class "Default")
      (node (ref "IC2") (pin "70") (pinfunction "(ALE)PG2_70") (pintype "bidirectional"))
    )
    (net (code "132") (name "unconnected-(IC2-(CLKO{slash}ICP3{slash}INT7)PE7-Pad9)") (class "Default")
      (node (ref "IC2") (pin "9") (pinfunction "(CLKO/ICP3/INT7)PE7_9") (pintype "bidirectional"))
    )
    (net (code "133") (name "unconnected-(IC2-(ICP1)PD4-Pad47)") (class "Default")
      (node (ref "IC2") (pin "47") (pinfunction "(ICP1)PD4_47") (pintype "bidirectional"))
    )
    (net (code "134") (name "unconnected-(IC2-(OC0A{slash}OC1C{slash}PCINT7)PB7-Pad26)") (class "Default")
      (node (ref "IC2") (pin "26") (pinfunction "(OC0A/OC1C/PCINT7)PB7_26") (pintype "bidirectional"))
    )
    (net (code "135") (name "unconnected-(IC2-(OC0B)PG5-Pad1)") (class "Default")
      (node (ref "IC2") (pin "1") (pinfunction "(OC0B)PG5_1") (pintype "bidirectional"))
    )
    (net (code "136") (name "unconnected-(IC2-(OC1A{slash}PCINT5)PB5-Pad24)") (class "Default")
      (node (ref "IC2") (pin "24") (pinfunction "(OC1A/PCINT5)PB5_24") (pintype "bidirectional"))
    )
    (net (code "137") (name "unconnected-(IC2-(OC1B{slash}PCINT6)PB6-Pad25)") (class "Default")
      (node (ref "IC2") (pin "25") (pinfunction "(OC1B/PCINT6)PB6_25") (pintype "bidirectional"))
    )
    (net (code "138") (name "unconnected-(IC2-(OC3B{slash}INT4)PE4-Pad6)") (class "Default")
      (node (ref "IC2") (pin "6") (pinfunction "(OC3B/INT4)PE4_6") (pintype "bidirectional"))
    )
    (net (code "139") (name "unconnected-(IC2-(RD)PG1-Pad52)") (class "Default")
      (node (ref "IC2") (pin "52") (pinfunction "(RD)PG1_52") (pintype "bidirectional"))
    )
    (net (code "140") (name "unconnected-(IC2-(T1)PD6-Pad49)") (class "Default")
      (node (ref "IC2") (pin "49") (pinfunction "(T1)PD6_49") (pintype "bidirectional"))
    )
    (net (code "141") (name "unconnected-(IC2-(T3{slash}INT6)PE6-Pad8)") (class "Default")
      (node (ref "IC2") (pin "8") (pinfunction "(T3/INT6)PE6_8") (pintype "bidirectional"))
    )
    (net (code "142") (name "unconnected-(IC2-(TOSC1)PG4-Pad29)") (class "Default")
      (node (ref "IC2") (pin "29") (pinfunction "(TOSC1)PG4_29") (pintype "bidirectional"))
    )
    (net (code "143") (name "unconnected-(IC2-(TOSC2)PG3-Pad28)") (class "Default")
      (node (ref "IC2") (pin "28") (pinfunction "(TOSC2)PG3_28") (pintype "bidirectional"))
    )
    (net (code "144") (name "unconnected-(IC2-(WR)PG0-Pad51)") (class "Default")
      (node (ref "IC2") (pin "51") (pinfunction "(WR)PG0_51") (pintype "bidirectional"))
    )
    (net (code "145") (name "unconnected-(IC2-(XCK0{slash}AIN0)PE2-Pad4)") (class "Default")
      (node (ref "IC2") (pin "4") (pinfunction "(XCK0/AIN0)PE2_4") (pintype "bidirectional"))
    )
    (net (code "146") (name "unconnected-(IC2-(XCK1)PD5-Pad48)") (class "Default")
      (node (ref "IC2") (pin "48") (pinfunction "(XCK1)PD5_48") (pintype "bidirectional"))
    )
    (net (code "147") (name "unconnected-(IC2-AREF-Pad98)") (class "Default")
      (node (ref "IC2") (pin "98") (pinfunction "AREF_98") (pintype "bidirectional"))
    )
    (net (code "148") (name "unconnected-(IC2-PH0(RXD2)-Pad12)") (class "Default")
      (node (ref "IC2") (pin "12") (pinfunction "PH0(RXD2)_12") (pintype "bidirectional"))
    )
    (net (code "149") (name "unconnected-(IC2-PH1(TXD2)-Pad13)") (class "Default")
      (node (ref "IC2") (pin "13") (pinfunction "PH1(TXD2)_13") (pintype "bidirectional"))
    )
    (net (code "150") (name "unconnected-(IC2-PH2(XCK2)-Pad14)") (class "Default")
      (node (ref "IC2") (pin "14") (pinfunction "PH2(XCK2)_14") (pintype "bidirectional"))
    )
    (net (code "151") (name "unconnected-(IC2-PH3(OC4A)-Pad15)") (class "Default")
      (node (ref "IC2") (pin "15") (pinfunction "PH3(OC4A)_15") (pintype "bidirectional"))
    )
    (net (code "152") (name "unconnected-(IC2-PH4(OC4B)-Pad16)") (class "Default")
      (node (ref "IC2") (pin "16") (pinfunction "PH4(OC4B)_16") (pintype "bidirectional"))
    )
    (net (code "153") (name "unconnected-(IC2-PH5(OC4C)-Pad17)") (class "Default")
      (node (ref "IC2") (pin "17") (pinfunction "PH5(OC4C)_17") (pintype "bidirectional"))
    )
    (net (code "154") (name "unconnected-(IC2-PH7(T4)-Pad27)") (class "Default")
      (node (ref "IC2") (pin "27") (pinfunction "PH7(T4)_27") (pintype "bidirectional"))
    )
    (net (code "155") (name "unconnected-(IC2-PJ1(TXD3{slash}PCINT10)-Pad64)") (class "Default")
      (node (ref "IC2") (pin "64") (pinfunction "PJ1(TXD3/PCINT10)_64") (pintype "bidirectional"))
    )
    (net (code "156") (name "unconnected-(IC2-PJ2(XCK3{slash}PCINT11)-Pad65)") (class "Default")
      (node (ref "IC2") (pin "65") (pinfunction "PJ2(XCK3/PCINT11)_65") (pintype "bidirectional"))
    )
    (net (code "157") (name "unconnected-(IC2-PJ3(PCINT12)-Pad66)") (class "Default")
      (node (ref "IC2") (pin "66") (pinfunction "PJ3(PCINT12)_66") (pintype "bidirectional"))
    )
    (net (code "158") (name "unconnected-(IC2-PJ4(PCINT13)-Pad67)") (class "Default")
      (node (ref "IC2") (pin "67") (pinfunction "PJ4(PCINT13)_67") (pintype "bidirectional"))
    )
    (net (code "159") (name "unconnected-(IC2-PJ5(PCINT14)-Pad68)") (class "Default")
      (node (ref "IC2") (pin "68") (pinfunction "PJ5(PCINT14)_68") (pintype "bidirectional"))
    )
    (net (code "160") (name "unconnected-(IC2-PJ6(PCINT15)-Pad69)") (class "Default")
      (node (ref "IC2") (pin "69") (pinfunction "PJ6(PCINT15)_69") (pintype "bidirectional"))
    )
    (net (code "161") (name "unconnected-(IC2-PJ7-Pad79)") (class "Default")
      (node (ref "IC2") (pin "79") (pinfunction "PJ7_79") (pintype "bidirectional"))
    )
    (net (code "162") (name "unconnected-(IC2-PK0(ADC8{slash}PCINT16)-Pad89)") (class "Default")
      (node (ref "IC2") (pin "89") (pinfunction "PK0(ADC8/PCINT16)_89") (pintype "bidirectional"))
    )
    (net (code "163") (name "unconnected-(IC2-PK1(ADC9{slash}PCINT17)-Pad88)") (class "Default")
      (node (ref "IC2") (pin "88") (pinfunction "PK1(ADC9/PCINT17)_88") (pintype "bidirectional"))
    )
    (net (code "164") (name "unconnected-(IC2-PK2(ADC10{slash}PCINT18)-Pad87)") (class "Default")
      (node (ref "IC2") (pin "87") (pinfunction "PK2(ADC10/PCINT18)_87") (pintype "bidirectional"))
    )
    (net (code "165") (name "unconnected-(IC2-PK3(ADC11{slash}PCINT19)-Pad86)") (class "Default")
      (node (ref "IC2") (pin "86") (pinfunction "PK3(ADC11/PCINT19)_86") (pintype "bidirectional"))
    )
    (net (code "166") (name "unconnected-(IC2-PK4(ADC12{slash}PCINT20)-Pad85)") (class "Default")
      (node (ref "IC2") (pin "85") (pinfunction "PK4(ADC12/PCINT20)_85") (pintype "bidirectional"))
    )
    (net (code "167") (name "unconnected-(IC2-PK5(ADC13{slash}PCINT21)-Pad84)") (class "Default")
      (node (ref "IC2") (pin "84") (pinfunction "PK5(ADC13/PCINT21)_84") (pintype "bidirectional"))
    )
    (net (code "168") (name "unconnected-(IC2-PK6(ADC14{slash}PCINT22)-Pad83)") (class "Default")
      (node (ref "IC2") (pin "83") (pinfunction "PK6(ADC14/PCINT22)_83") (pintype "bidirectional"))
    )
    (net (code "169") (name "unconnected-(IC2-PK7(ADC15{slash}PCINT23)-Pad82)") (class "Default")
      (node (ref "IC2") (pin "82") (pinfunction "PK7(ADC15/PCINT23)_82") (pintype "bidirectional"))
    )
    (net (code "170") (name "unconnected-(IC2-PL4(OC5B)-Pad39)") (class "Default")
      (node (ref "IC2") (pin "39") (pinfunction "PL4(OC5B)_39") (pintype "bidirectional"))
    )
    (net (code "171") (name "unconnected-(IC2-PL5(OC5C)-Pad40)") (class "Default")
      (node (ref "IC2") (pin "40") (pinfunction "PL5(OC5C)_40") (pintype "bidirectional"))
    )
    (net (code "172") (name "unconnected-(IC2-PL6-Pad41)") (class "Default")
      (node (ref "IC2") (pin "41") (pinfunction "PL6_41") (pintype "bidirectional"))
    )
    (net (code "173") (name "unconnected-(IC2-PL7-Pad42)") (class "Default")
      (node (ref "IC2") (pin "42") (pinfunction "PL7_42") (pintype "bidirectional"))
    )
    (net (code "174") (name "unconnected-(IC7-CTS-Pad11)") (class "Default")
      (node (ref "IC7") (pin "11") (pinfunction "CTS_11") (pintype "input"))
    )
    (net (code "175") (name "unconnected-(IC7-DCD-Pad10)") (class "Default")
      (node (ref "IC7") (pin "10") (pinfunction "DCD_10") (pintype "input"))
    )
    (net (code "176") (name "unconnected-(IC7-DSR-Pad9)") (class "Default")
      (node (ref "IC7") (pin "9") (pinfunction "DSR_9") (pintype "input"))
    )
    (net (code "177") (name "unconnected-(IC7-OSCI-Pad27)") (class "Default")
      (node (ref "IC7") (pin "27") (pinfunction "OSCI_27") (pintype "input"))
    )
    (net (code "178") (name "unconnected-(IC7-OSCO-Pad28)") (class "Default")
      (node (ref "IC7") (pin "28") (pinfunction "OSCO_28") (pintype "output"))
    )
    (net (code "179") (name "unconnected-(IC7-PWREN-Pad14)") (class "Default")
      (node (ref "IC7") (pin "14") (pinfunction "PWREN_14") (pintype "input"))
    )
    (net (code "180") (name "unconnected-(IC7-RI-Pad6)") (class "Default")
      (node (ref "IC7") (pin "6") (pinfunction "RI_6") (pintype "input"))
    )
    (net (code "181") (name "unconnected-(IC7-RTS-Pad3)") (class "Default")
      (node (ref "IC7") (pin "3") (pinfunction "RTS_3") (pintype "output"))
    )
    (net (code "182") (name "unconnected-(IC7-SLEEP-Pad12)") (class "Default")
      (node (ref "IC7") (pin "12") (pinfunction "SLEEP_12") (pintype "input"))
    )
    (net (code "183") (name "unconnected-(IC7-TXDEN-Pad13)") (class "Default")
      (node (ref "IC7") (pin "13") (pinfunction "TXDEN_13") (pintype "input"))
    )
    (net (code "184") (name "unconnected-(K1-PadO)") (class "Default")
      (node (ref "K1") (pin "O") (pinfunction "O_O") (pintype "passive"))
    )
    (net (code "185") (name "unconnected-(K2-PadO)") (class "Default")
      (node (ref "K2") (pin "O") (pinfunction "O_O") (pintype "passive"))
    )
    (net (code "186") (name "unconnected-(K3-PadO)") (class "Default")
      (node (ref "K3") (pin "O") (pinfunction "O_O") (pintype "passive"))
    )
    (net (code "187") (name "unconnected-(K6-PadO)") (class "Default")
      (node (ref "K6") (pin "O") (pinfunction "O_O") (pintype "passive"))
    )
    (net (code "188") (name "unconnected-(Q1-C{slash}-Pad2@1)") (class "Default")
      (node (ref "Q1") (pin "2@1") (pinfunction "C/_2@1") (pintype "passive"))
    )
    (net (code "189") (name "unconnected-(Q2-C{slash}-Pad2@1)") (class "Default")
      (node (ref "Q2") (pin "2@1") (pinfunction "C/_2@1") (pintype "passive"))
    )
    (net (code "190") (name "unconnected-(U$2-D0{slash}RX1-PadD0)") (class "Default")
      (node (ref "U$2") (pin "D0") (pinfunction "D0/RX1_D0") (pintype "bidirectional"))
    )
    (net (code "191") (name "unconnected-(U$2-D1{slash}TX0-PadD1)") (class "Default")
      (node (ref "U$2") (pin "D1") (pinfunction "D1/TX0_D1") (pintype "bidirectional"))
    )
    (net (code "192") (name "unconnected-(U$2-D2{slash}FLAG-PadD2-FLAG)") (class "Default")
      (node (ref "U$2") (pin "D2-FLAG") (pinfunction "D2/FLAG_D2-FLAG") (pintype "bidirectional"))
    )
    (net (code "193") (name "unconnected-(U$2-D4{slash}BUSY-PadD4-BUSY)") (class "Default")
      (node (ref "U$2") (pin "D4-BUSY") (pinfunction "D4/BUSY_D4-BUSY") (pintype "bidirectional"))
    )
    (net (code "194") (name "unconnected-(U$2-D9{slash}STCK-PadD9-STCK)") (class "Default")
      (node (ref "U$2") (pin "D9-STCK") (pinfunction "D9/STCK_D9-STCK") (pintype "bidirectional"))
    )
    (net (code "195") (name "unconnected-(U$2-PadA0)") (class "Default")
      (node (ref "U$2") (pin "A0") (pinfunction "A0_A0") (pintype "bidirectional"))
    )
    (net (code "196") (name "unconnected-(U$2-PadA1)") (class "Default")
      (node (ref "U$2") (pin "A1") (pinfunction "A1_A1") (pintype "bidirectional"))
    )
    (net (code "197") (name "unconnected-(U$2-PadA3)") (class "Default")
      (node (ref "U$2") (pin "A3") (pinfunction "A3_A3") (pintype "bidirectional"))
    )
    (net (code "198") (name "unconnected-(U$2-PadA4)") (class "Default")
      (node (ref "U$2") (pin "A4") (pinfunction "A4_A4") (pintype "bidirectional"))
    )
    (net (code "199") (name "unconnected-(U$2-PadA5)") (class "Default")
      (node (ref "U$2") (pin "A5") (pinfunction "A5_A5") (pintype "bidirectional"))
    )
    (net (code "200") (name "unconnected-(U$2-PadD3)") (class "Default")
      (node (ref "U$2") (pin "D3") (pinfunction "D3_D3") (pintype "bidirectional"))
    )
    (net (code "201") (name "unconnected-(U$2-PadD5)") (class "Default")
      (node (ref "U$2") (pin "D5") (pinfunction "D5_D5") (pintype "bidirectional"))
    )
    (net (code "202") (name "unconnected-(U$2-PadD6)") (class "Default")
      (node (ref "U$2") (pin "D6") (pinfunction "D6_D6") (pintype "bidirectional"))
    )
    (net (code "203") (name "unconnected-(U$2-PadD7)") (class "Default")
      (node (ref "U$2") (pin "D7") (pinfunction "D7_D7") (pintype "bidirectional"))
    )
    (net (code "204") (name "unconnected-(U$2-PadD10)") (class "Default")
      (node (ref "U$2") (pin "D10") (pinfunction "D10_D10") (pintype "bidirectional"))
    )
    (net (code "205") (name "unconnected-(U2-CR1-Pad3)") (class "Default")
      (node (ref "U2") (pin "3") (pinfunction "CR1_3") (pintype "input"))
    )
    (net (code "206") (name "unconnected-(U3-CLKOUT-Pad3)") (class "Default")
      (node (ref "U3") (pin "3") (pinfunction "CLKOUT_3") (pintype "output"))
    )
    (net (code "207") (name "unconnected-(U3-WOL-Pad5)") (class "Default")
      (node (ref "U3") (pin "5") (pinfunction "WOL_5") (pintype "output"))
    )
  )
)
